# schematic.net
KiCad netlist of a schematic drawn in Altium Designer
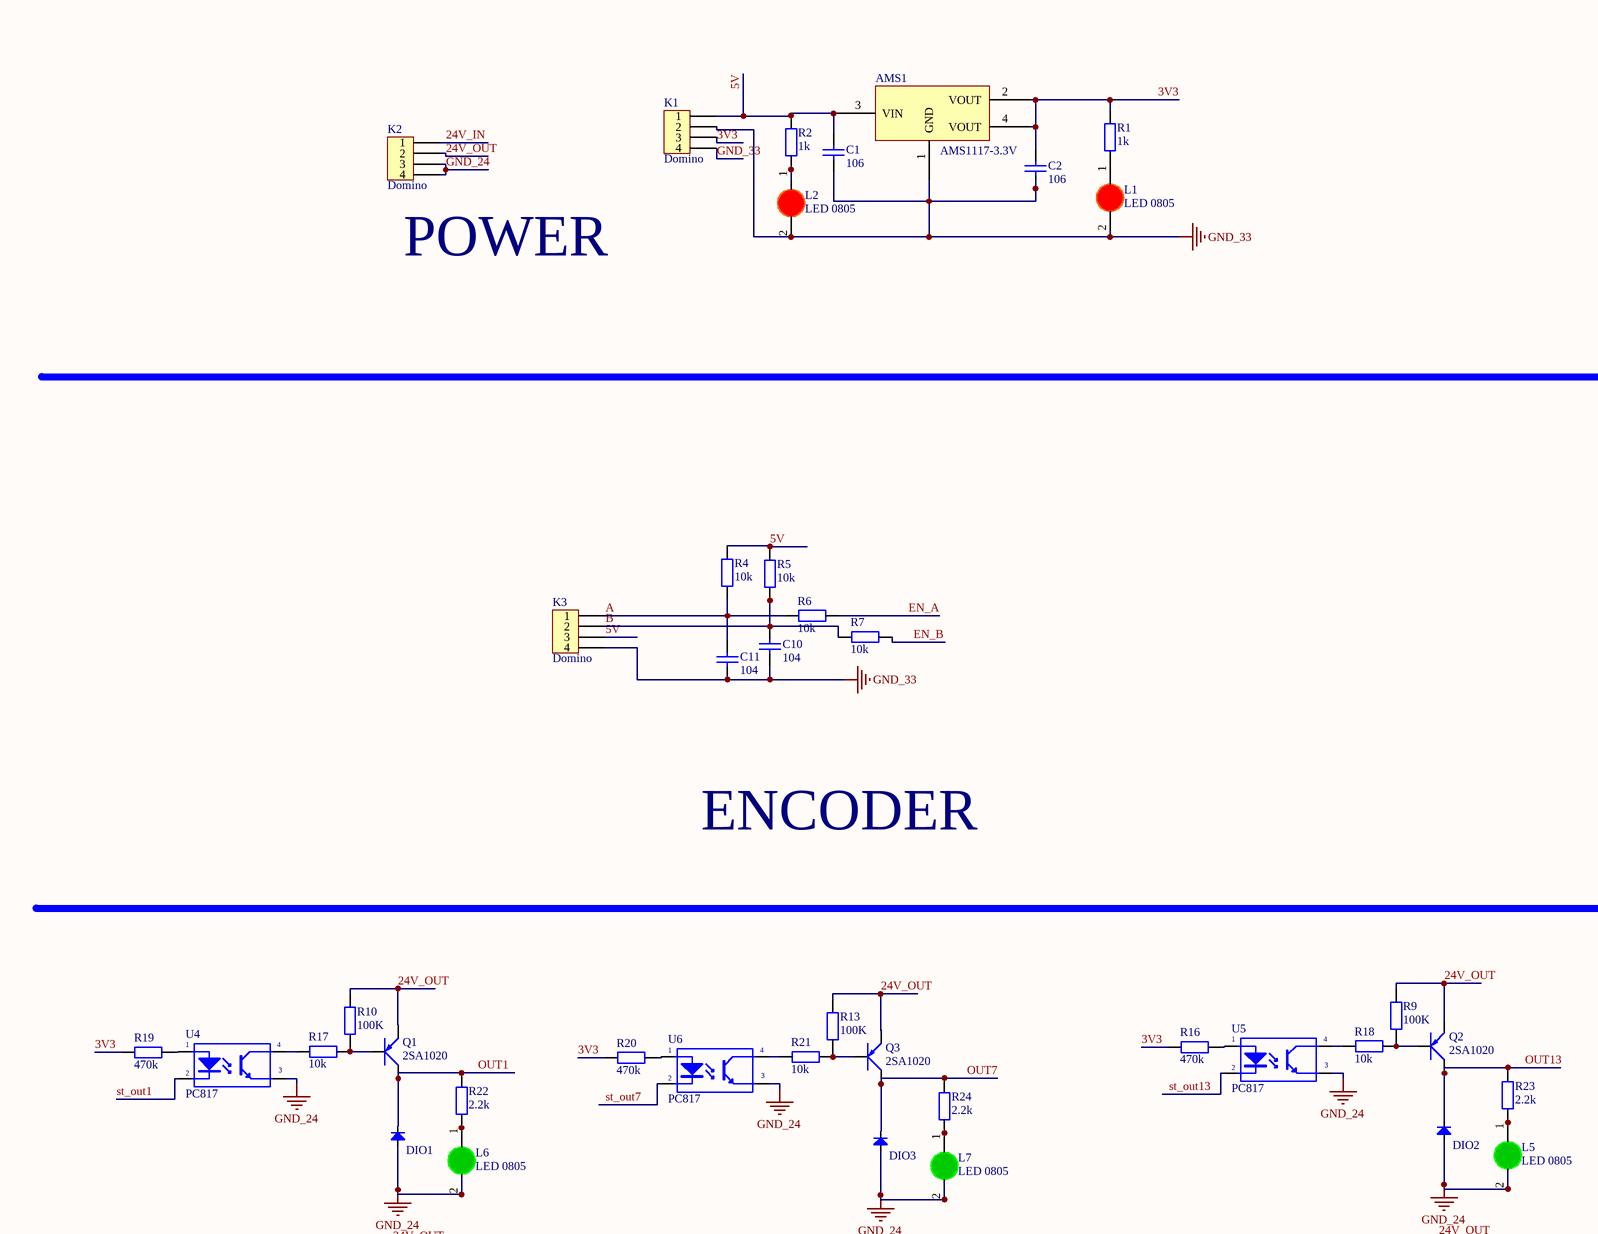
[diagram p0: schematic.SchDoc, top left]
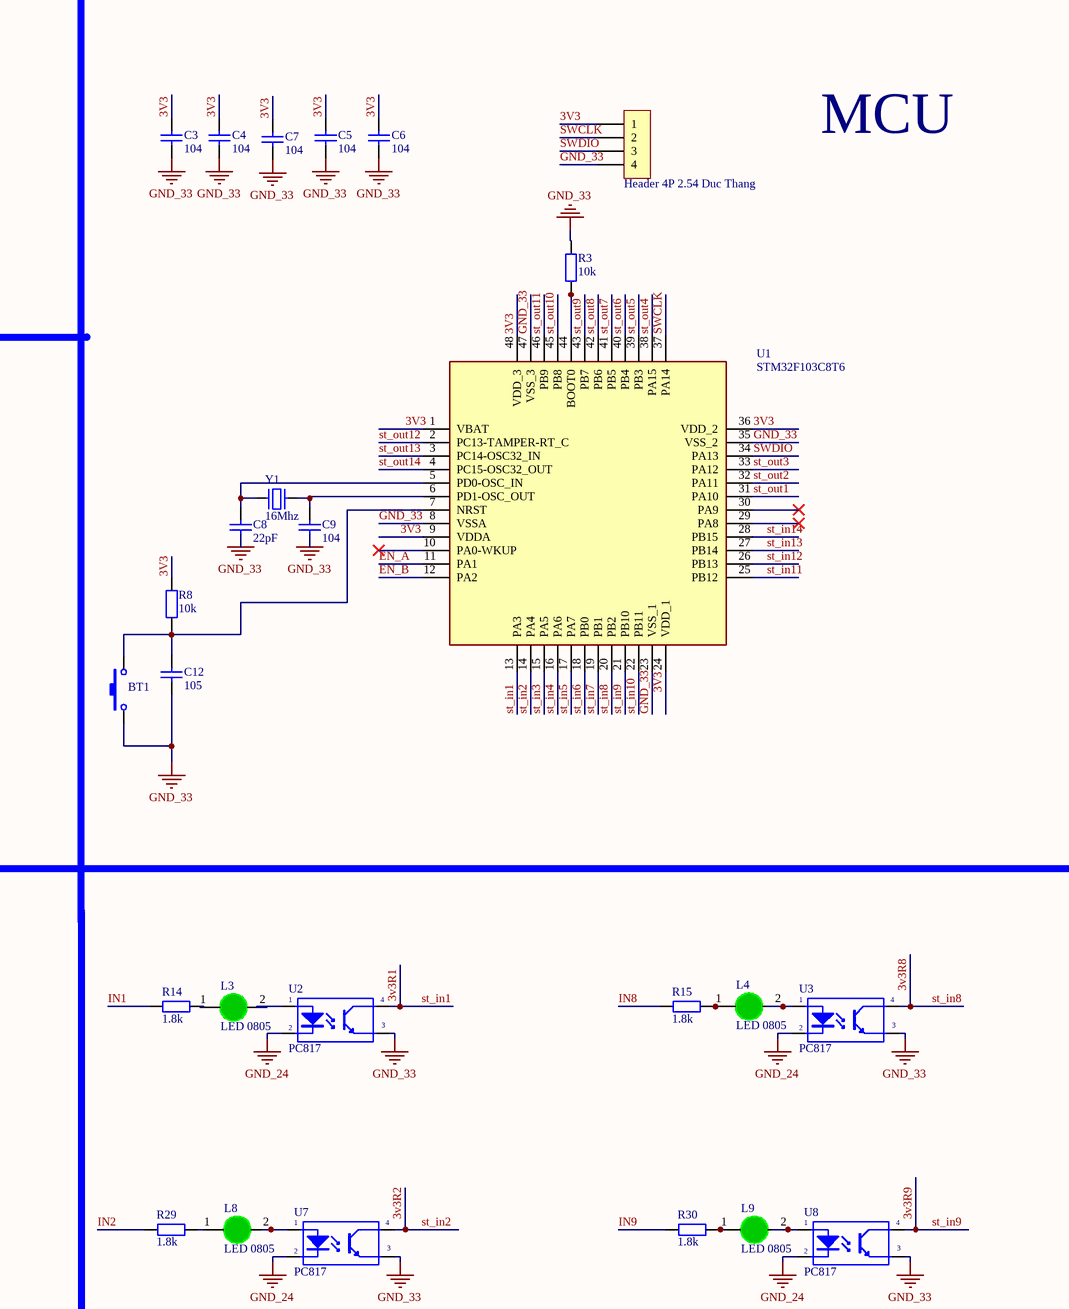
[diagram p1: schematic.SchDoc, top right]
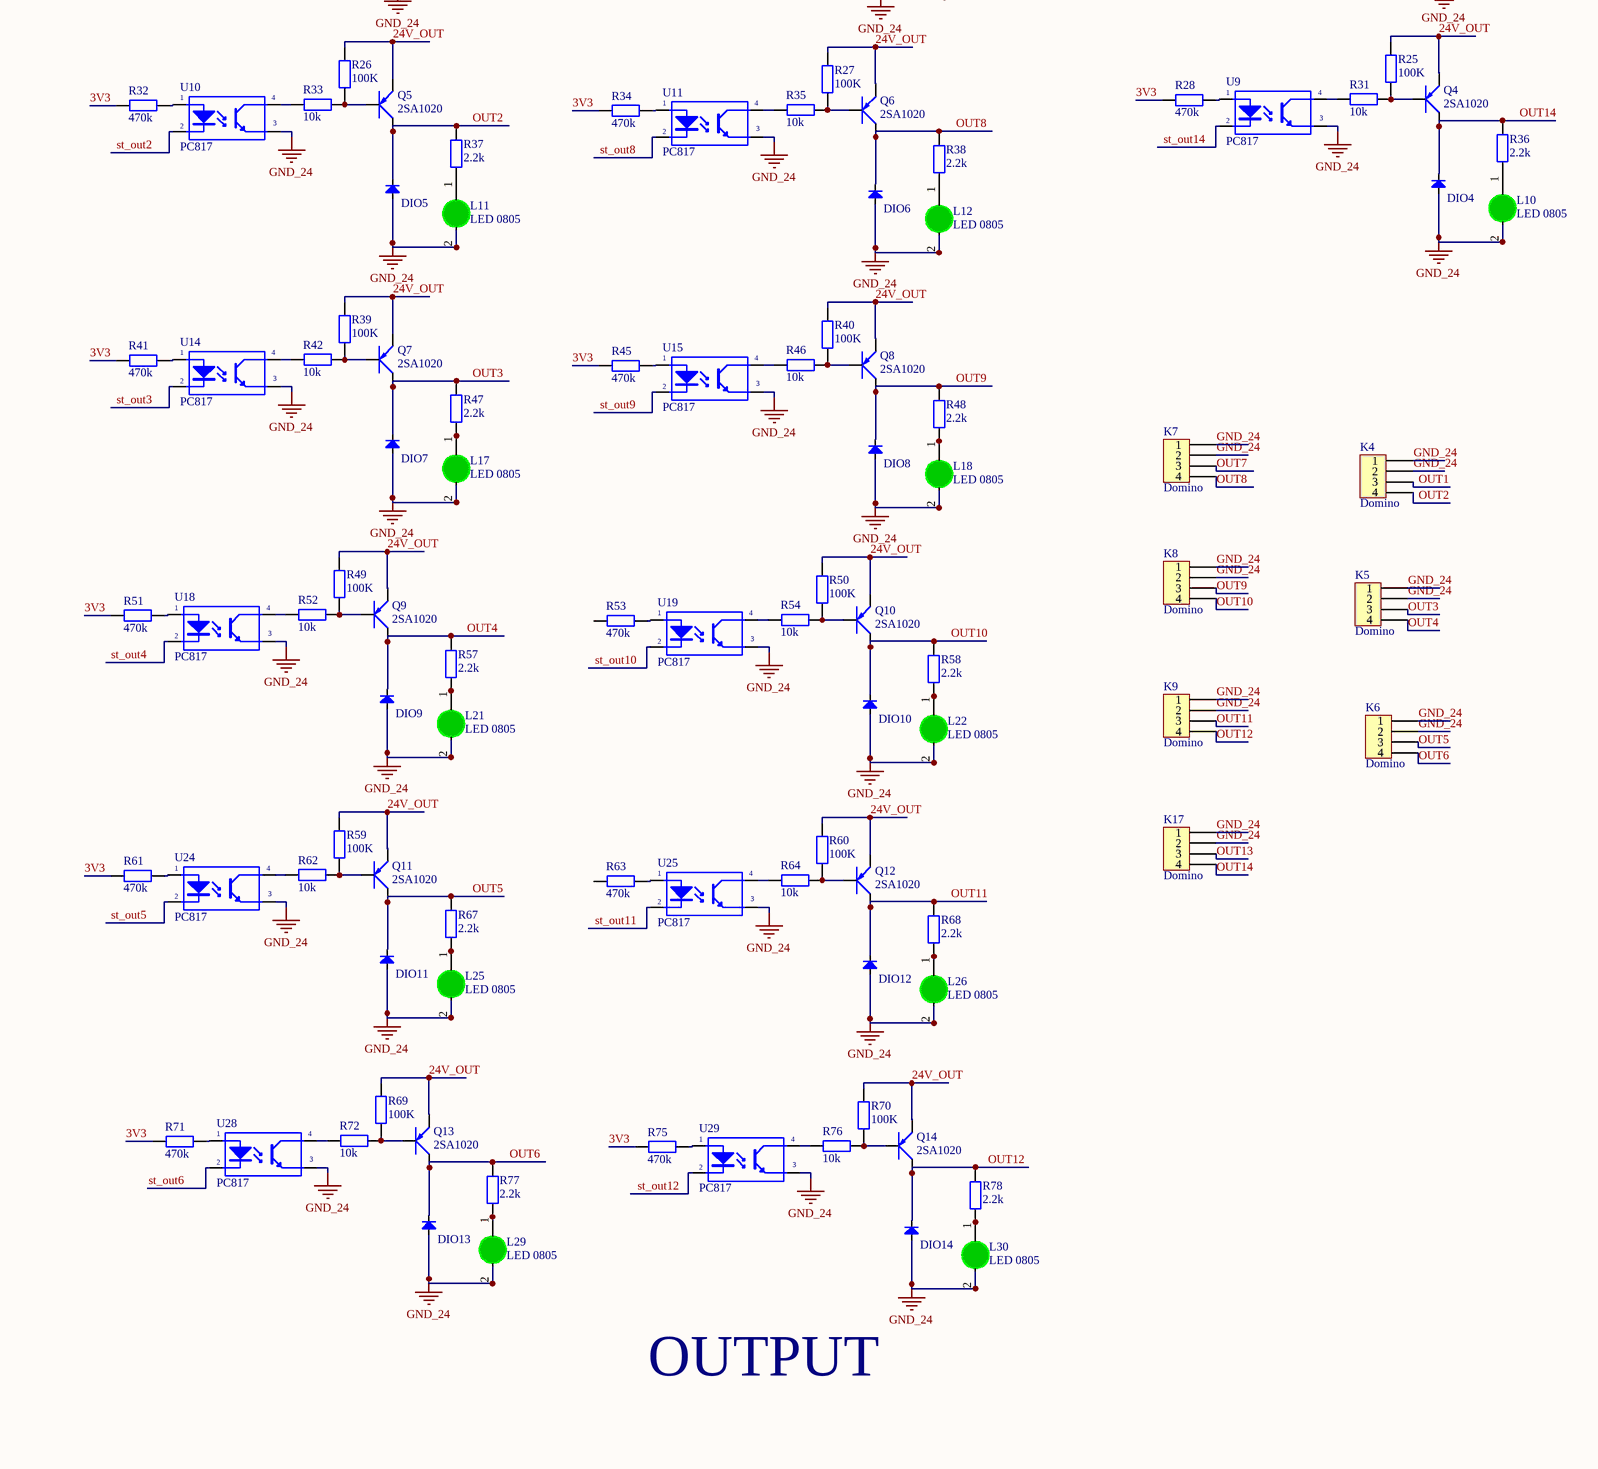
[diagram p2: schematic.SchDoc, bottom left]
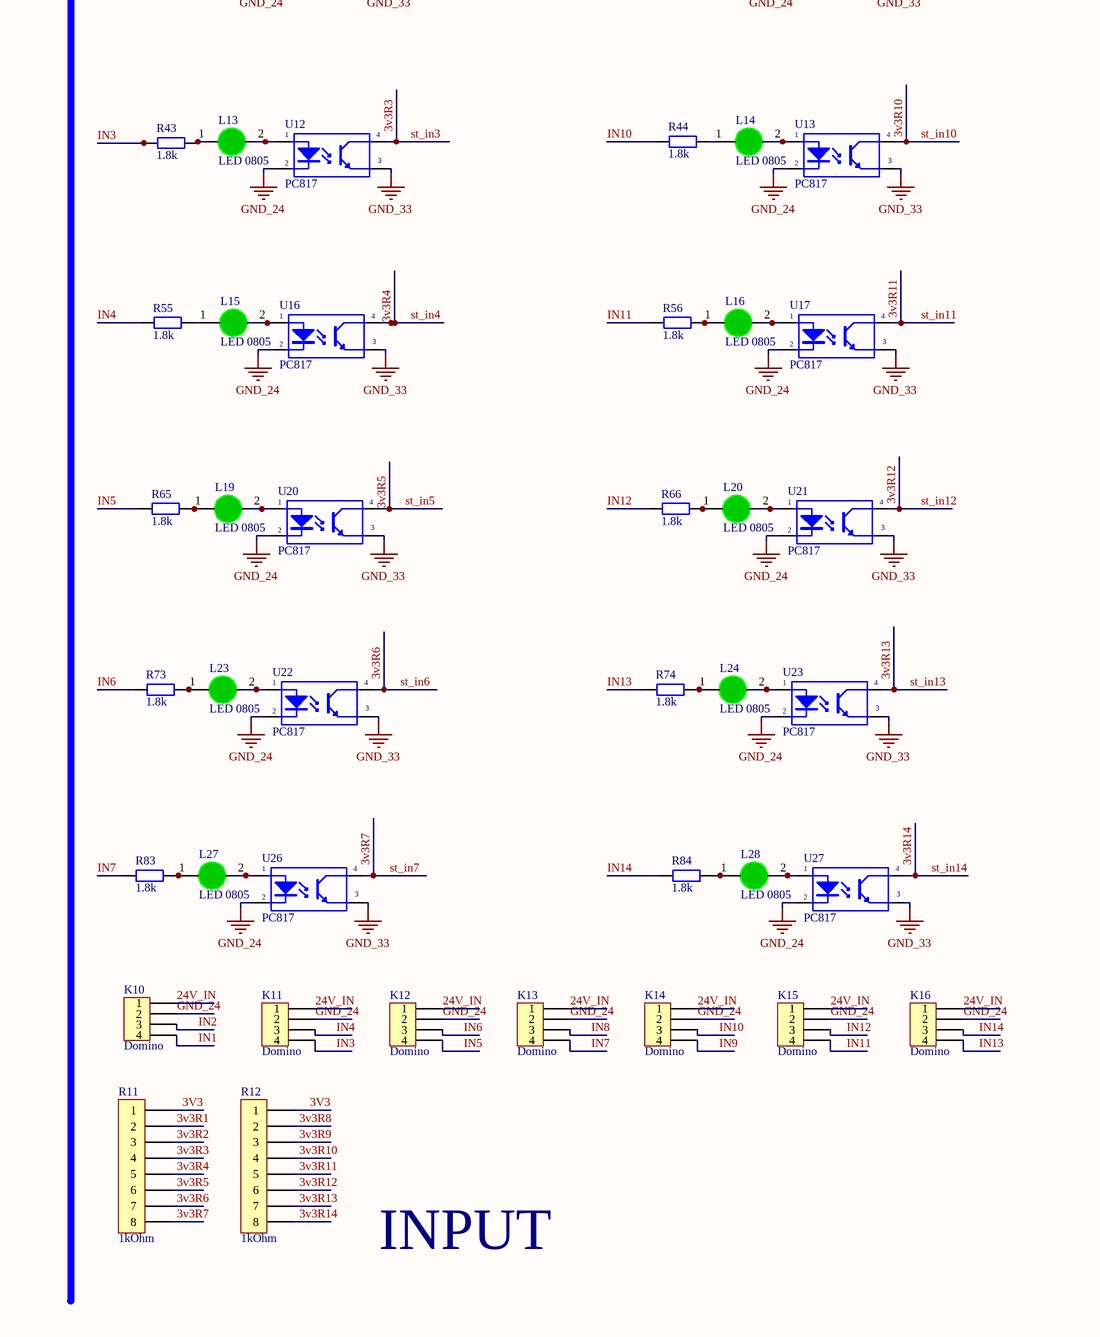
[diagram p3: schematic.SchDoc, bottom right]

(export (version "E")
  (design (tool "Eeschema 10.0.6"))
  (components
    (comp (ref "AMS1")
      (value "AMS1117-3.3V")
      (footprint "SOT223")
      (description "Dán")
      (libsource (lib "Altium_Lib_by_KhueNguyenCreator") (part "AMS1117 SMD"))
    )
    (comp (ref "BT1")
      (value "Nut Nhan 2 Chan SMD 3x6x2.5")
      (footprint "Nut Nhan 2 Chan SMD 3x6x2.5")
      (libsource (lib "Altium_Lib_by_KhueNguyenCreator") (part "Nut Nhan 2 Chan SMD 3x6x2.5"))
    )
    (comp (ref "C1")
      (value "106")
      (footprint "tu 1206")
      (description "Dán")
      (libsource (lib "Altium_Lib_by_KhueNguyenCreator") (part "Tu 1206 106 16V 20%"))
    )
    (comp (ref "C2")
      (value "106")
      (footprint "tu 1206")
      (description "Dán")
      (libsource (lib "Altium_Lib_by_KhueNguyenCreator") (part "Tu 1206 106 16V 20%"))
    )
    (comp (ref "C3")
      (value "104")
      (footprint "tu 1206")
      (description "Dán")
      (libsource (lib "Altium_Lib_by_KhueNguyenCreator") (part "Tu 1206 104 50V 20%"))
    )
    (comp (ref "C4")
      (value "104")
      (footprint "tu 1206")
      (description "Dán")
      (libsource (lib "Altium_Lib_by_KhueNguyenCreator") (part "Tu 1206 104 50V 20%"))
    )
    (comp (ref "C5")
      (value "104")
      (footprint "tu 1206")
      (description "Dán")
      (libsource (lib "Altium_Lib_by_KhueNguyenCreator") (part "Tu 1206 104 50V 20%"))
    )
    (comp (ref "C6")
      (value "104")
      (footprint "tu 1206")
      (description "Dán")
      (libsource (lib "Altium_Lib_by_KhueNguyenCreator") (part "Tu 1206 104 50V 20%"))
    )
    (comp (ref "C7")
      (value "104")
      (footprint "tu 1206")
      (description "Dán")
      (libsource (lib "Altium_Lib_by_KhueNguyenCreator") (part "Tu 1206 104 50V 20%"))
    )
    (comp (ref "C8")
      (value "22pF")
      (footprint "tu 1206")
      (description "Dán")
      (libsource (lib "Altium_Lib_by_KhueNguyenCreator") (part "Tu 1206 22pF 50V 10%"))
    )
    (comp (ref "C9")
      (value "104")
      (footprint "tu 1206")
      (description "Dán")
      (libsource (lib "Altium_Lib_by_KhueNguyenCreator") (part "Tu 1206 104 50V 20%"))
    )
    (comp (ref "C10")
      (value "104")
      (footprint "tu 1206")
      (description "Dán")
      (libsource (lib "Altium_Lib_by_KhueNguyenCreator") (part "Tu 1206 104 50V 20%"))
    )
    (comp (ref "C11")
      (value "104")
      (footprint "tu 1206")
      (description "Dán")
      (libsource (lib "Altium_Lib_by_KhueNguyenCreator") (part "Tu 1206 104 50V 20%"))
    )
    (comp (ref "C12")
      (value "105")
      (footprint "tu 1206")
      (description "Dán")
      (libsource (lib "Altium_Lib_by_KhueNguyenCreator") (part "Tu 1206 105 50V 20%"))
    )
    (comp (ref "DIO1")
      (value "Diode SMD")
      (footprint "DIO-SMD-123")
      (description "Default Diode")
      (fields (field (name "PUBLISHER") "Altium Limited"))
      (libsource (lib "TechMT.VN_Lib_Project v2") (part "Diode SMD"))
    )
    (comp (ref "DIO2")
      (value "Diode SMD")
      (footprint "DIO-SMD-123")
      (description "Default Diode")
      (fields (field (name "PUBLISHER") "Altium Limited"))
      (libsource (lib "TechMT.VN_Lib_Project v2") (part "Diode SMD"))
    )
    (comp (ref "DIO3")
      (value "Diode SMD")
      (footprint "DIO-SMD-123")
      (description "Default Diode")
      (fields (field (name "PUBLISHER") "Altium Limited"))
      (libsource (lib "TechMT.VN_Lib_Project v2") (part "Diode SMD"))
    )
    (comp (ref "DIO4")
      (value "Diode SMD")
      (footprint "DIO-SMD-123")
      (description "Default Diode")
      (fields (field (name "PUBLISHER") "Altium Limited"))
      (libsource (lib "TechMT.VN_Lib_Project v2") (part "Diode SMD"))
    )
    (comp (ref "DIO5")
      (value "Diode SMD")
      (footprint "DIO-SMD-123")
      (description "Default Diode")
      (fields (field (name "PUBLISHER") "Altium Limited"))
      (libsource (lib "TechMT.VN_Lib_Project v2") (part "Diode SMD"))
    )
    (comp (ref "DIO6")
      (value "Diode SMD")
      (footprint "DIO-SMD-123")
      (description "Default Diode")
      (fields (field (name "PUBLISHER") "Altium Limited"))
      (libsource (lib "TechMT.VN_Lib_Project v2") (part "Diode SMD"))
    )
    (comp (ref "DIO7")
      (value "Diode SMD")
      (footprint "DIO-SMD-123")
      (description "Default Diode")
      (fields (field (name "PUBLISHER") "Altium Limited"))
      (libsource (lib "TechMT.VN_Lib_Project v2") (part "Diode SMD"))
    )
    (comp (ref "DIO8")
      (value "Diode SMD")
      (footprint "DIO-SMD-123")
      (description "Default Diode")
      (fields (field (name "PUBLISHER") "Altium Limited"))
      (libsource (lib "TechMT.VN_Lib_Project v2") (part "Diode SMD"))
    )
    (comp (ref "DIO9")
      (value "Diode SMD")
      (footprint "DIO-SMD-123")
      (description "Default Diode")
      (fields (field (name "PUBLISHER") "Altium Limited"))
      (libsource (lib "TechMT.VN_Lib_Project v2") (part "Diode SMD"))
    )
    (comp (ref "DIO10")
      (value "Diode SMD")
      (footprint "DIO-SMD-123")
      (description "Default Diode")
      (fields (field (name "PUBLISHER") "Altium Limited"))
      (libsource (lib "TechMT.VN_Lib_Project v2") (part "Diode SMD"))
    )
    (comp (ref "DIO11")
      (value "Diode SMD")
      (footprint "DIO-SMD-123")
      (description "Default Diode")
      (fields (field (name "PUBLISHER") "Altium Limited"))
      (libsource (lib "TechMT.VN_Lib_Project v2") (part "Diode SMD"))
    )
    (comp (ref "DIO12")
      (value "Diode SMD")
      (footprint "DIO-SMD-123")
      (description "Default Diode")
      (fields (field (name "PUBLISHER") "Altium Limited"))
      (libsource (lib "TechMT.VN_Lib_Project v2") (part "Diode SMD"))
    )
    (comp (ref "DIO13")
      (value "Diode SMD")
      (footprint "DIO-SMD-123")
      (description "Default Diode")
      (fields (field (name "PUBLISHER") "Altium Limited"))
      (libsource (lib "TechMT.VN_Lib_Project v2") (part "Diode SMD"))
    )
    (comp (ref "DIO14")
      (value "Diode SMD")
      (footprint "DIO-SMD-123")
      (description "Default Diode")
      (fields (field (name "PUBLISHER") "Altium Limited"))
      (libsource (lib "TechMT.VN_Lib_Project v2") (part "Diode SMD"))
    )
    (comp (ref "H1")
      (value "Header 4P 2.54 Duc Thang")
      (footprint "XH2.54M-4")
      (description "Cắm")
      (libsource (lib "Altium_Lib_by_KhueNguyenCreator") (part "Header 4P 2.54 Duc Thang"))
    )
    (comp (ref "K1") (value "Domino") (footprint "KF128HL_2P") (libsource (lib "My_lib") (part "KF128HL_2P")))
    (comp (ref "K2") (value "Domino") (footprint "KF128HL_2P") (libsource (lib "My_lib") (part "KF128HL_2P")))
    (comp (ref "K3") (value "Domino") (footprint "KF128HL_2P") (libsource (lib "My_lib") (part "KF128HL_2P")))
    (comp (ref "K4") (value "Domino") (footprint "KF128HL_2P") (libsource (lib "My_lib") (part "KF128HL_2P")))
    (comp (ref "K5") (value "Domino") (footprint "KF128HL_2P") (libsource (lib "My_lib") (part "KF128HL_2P")))
    (comp (ref "K6") (value "Domino") (footprint "KF128HL_2P") (libsource (lib "My_lib") (part "KF128HL_2P")))
    (comp (ref "K7") (value "Domino") (footprint "KF128HL_2P") (libsource (lib "My_lib") (part "KF128HL_2P")))
    (comp (ref "K8") (value "Domino") (footprint "KF128HL_2P") (libsource (lib "My_lib") (part "KF128HL_2P")))
    (comp (ref "K9") (value "Domino") (footprint "KF128HL_2P") (libsource (lib "My_lib") (part "KF128HL_2P")))
    (comp (ref "K10")
      (value "Domino")
      (footprint "KF128HL_2P")
      (libsource (lib "My_lib") (part "KF128HL_2P"))
    )
    (comp (ref "K11")
      (value "Domino")
      (footprint "KF128HL_2P")
      (libsource (lib "My_lib") (part "KF128HL_2P"))
    )
    (comp (ref "K12")
      (value "Domino")
      (footprint "KF128HL_2P")
      (libsource (lib "My_lib") (part "KF128HL_2P"))
    )
    (comp (ref "K13")
      (value "Domino")
      (footprint "KF128HL_2P")
      (libsource (lib "My_lib") (part "KF128HL_2P"))
    )
    (comp (ref "K14")
      (value "Domino")
      (footprint "KF128HL_2P")
      (libsource (lib "My_lib") (part "KF128HL_2P"))
    )
    (comp (ref "K15")
      (value "Domino")
      (footprint "KF128HL_2P")
      (libsource (lib "My_lib") (part "KF128HL_2P"))
    )
    (comp (ref "K16")
      (value "Domino")
      (footprint "KF128HL_2P")
      (libsource (lib "My_lib") (part "KF128HL_2P"))
    )
    (comp (ref "K17")
      (value "Domino")
      (footprint "KF128HL_2P")
      (libsource (lib "My_lib") (part "KF128HL_2P"))
    )
    (comp (ref "L1")
      (value "LED 0805")
      (footprint "LED-1206-Red")
      (description "Dán")
      (libsource (lib "Altium_Lib_by_KhueNguyenCreator") (part "LED 1206 Do"))
    )
    (comp (ref "L2")
      (value "LED 0805")
      (footprint "LED-1206-Red")
      (description "Dán")
      (libsource (lib "Altium_Lib_by_KhueNguyenCreator") (part "LED 1206 Do"))
    )
    (comp (ref "L3")
      (value "LED 0805")
      (footprint "LED-1206-Green")
      (description "Dán")
      (libsource (lib "Altium_Lib_by_KhueNguyenCreator") (part "LED 1206 Xanh La"))
    )
    (comp (ref "L4")
      (value "LED 0805")
      (footprint "LED-1206-Green")
      (description "Dán")
      (libsource (lib "Altium_Lib_by_KhueNguyenCreator") (part "LED 1206 Xanh La"))
    )
    (comp (ref "L5")
      (value "LED 0805")
      (footprint "LED-1206-Green")
      (description "Dán")
      (libsource (lib "Altium_Lib_by_KhueNguyenCreator") (part "LED 1206 Xanh La"))
    )
    (comp (ref "L6")
      (value "LED 0805")
      (footprint "LED-1206-Green")
      (description "Dán")
      (libsource (lib "Altium_Lib_by_KhueNguyenCreator") (part "LED 1206 Xanh La"))
    )
    (comp (ref "L7")
      (value "LED 0805")
      (footprint "LED-1206-Green")
      (description "Dán")
      (libsource (lib "Altium_Lib_by_KhueNguyenCreator") (part "LED 1206 Xanh La"))
    )
    (comp (ref "L8")
      (value "LED 0805")
      (footprint "LED-1206-Green")
      (description "Dán")
      (libsource (lib "Altium_Lib_by_KhueNguyenCreator") (part "LED 1206 Xanh La"))
    )
    (comp (ref "L9")
      (value "LED 0805")
      (footprint "LED-1206-Green")
      (description "Dán")
      (libsource (lib "Altium_Lib_by_KhueNguyenCreator") (part "LED 1206 Xanh La"))
    )
    (comp (ref "L10")
      (value "LED 0805")
      (footprint "LED-1206-Green")
      (description "Dán")
      (libsource (lib "Altium_Lib_by_KhueNguyenCreator") (part "LED 1206 Xanh La"))
    )
    (comp (ref "L11")
      (value "LED 0805")
      (footprint "LED-1206-Green")
      (description "Dán")
      (libsource (lib "Altium_Lib_by_KhueNguyenCreator") (part "LED 1206 Xanh La"))
    )
    (comp (ref "L12")
      (value "LED 0805")
      (footprint "LED-1206-Green")
      (description "Dán")
      (libsource (lib "Altium_Lib_by_KhueNguyenCreator") (part "LED 1206 Xanh La"))
    )
    (comp (ref "L13")
      (value "LED 0805")
      (footprint "LED-1206-Green")
      (description "Dán")
      (libsource (lib "Altium_Lib_by_KhueNguyenCreator") (part "LED 1206 Xanh La"))
    )
    (comp (ref "L14")
      (value "LED 0805")
      (footprint "LED-1206-Green")
      (description "Dán")
      (libsource (lib "Altium_Lib_by_KhueNguyenCreator") (part "LED 1206 Xanh La"))
    )
    (comp (ref "L15")
      (value "LED 0805")
      (footprint "LED-1206-Green")
      (description "Dán")
      (libsource (lib "Altium_Lib_by_KhueNguyenCreator") (part "LED 1206 Xanh La"))
    )
    (comp (ref "L16")
      (value "LED 0805")
      (footprint "LED-1206-Green")
      (description "Dán")
      (libsource (lib "Altium_Lib_by_KhueNguyenCreator") (part "LED 1206 Xanh La"))
    )
    (comp (ref "L17")
      (value "LED 0805")
      (footprint "LED-1206-Green")
      (description "Dán")
      (libsource (lib "Altium_Lib_by_KhueNguyenCreator") (part "LED 1206 Xanh La"))
    )
    (comp (ref "L18")
      (value "LED 0805")
      (footprint "LED-1206-Green")
      (description "Dán")
      (libsource (lib "Altium_Lib_by_KhueNguyenCreator") (part "LED 1206 Xanh La"))
    )
    (comp (ref "L19")
      (value "LED 0805")
      (footprint "LED-1206-Green")
      (description "Dán")
      (libsource (lib "Altium_Lib_by_KhueNguyenCreator") (part "LED 1206 Xanh La"))
    )
    (comp (ref "L20")
      (value "LED 0805")
      (footprint "LED-1206-Green")
      (description "Dán")
      (libsource (lib "Altium_Lib_by_KhueNguyenCreator") (part "LED 1206 Xanh La"))
    )
    (comp (ref "L21")
      (value "LED 0805")
      (footprint "LED-1206-Green")
      (description "Dán")
      (libsource (lib "Altium_Lib_by_KhueNguyenCreator") (part "LED 1206 Xanh La"))
    )
    (comp (ref "L22")
      (value "LED 0805")
      (footprint "LED-1206-Green")
      (description "Dán")
      (libsource (lib "Altium_Lib_by_KhueNguyenCreator") (part "LED 1206 Xanh La"))
    )
    (comp (ref "L23")
      (value "LED 0805")
      (footprint "LED-1206-Green")
      (description "Dán")
      (libsource (lib "Altium_Lib_by_KhueNguyenCreator") (part "LED 1206 Xanh La"))
    )
    (comp (ref "L24")
      (value "LED 0805")
      (footprint "LED-1206-Green")
      (description "Dán")
      (libsource (lib "Altium_Lib_by_KhueNguyenCreator") (part "LED 1206 Xanh La"))
    )
    (comp (ref "L25")
      (value "LED 0805")
      (footprint "LED-1206-Green")
      (description "Dán")
      (libsource (lib "Altium_Lib_by_KhueNguyenCreator") (part "LED 1206 Xanh La"))
    )
    (comp (ref "L26")
      (value "LED 0805")
      (footprint "LED-1206-Green")
      (description "Dán")
      (libsource (lib "Altium_Lib_by_KhueNguyenCreator") (part "LED 1206 Xanh La"))
    )
    (comp (ref "L27")
      (value "LED 0805")
      (footprint "LED-1206-Green")
      (description "Dán")
      (libsource (lib "Altium_Lib_by_KhueNguyenCreator") (part "LED 1206 Xanh La"))
    )
    (comp (ref "L28")
      (value "LED 0805")
      (footprint "LED-1206-Green")
      (description "Dán")
      (libsource (lib "Altium_Lib_by_KhueNguyenCreator") (part "LED 1206 Xanh La"))
    )
    (comp (ref "L29")
      (value "LED 0805")
      (footprint "LED-1206-Green")
      (description "Dán")
      (libsource (lib "Altium_Lib_by_KhueNguyenCreator") (part "LED 1206 Xanh La"))
    )
    (comp (ref "L30")
      (value "LED 0805")
      (footprint "LED-1206-Green")
      (description "Dán")
      (libsource (lib "Altium_Lib_by_KhueNguyenCreator") (part "LED 1206 Xanh La"))
    )
    (comp (ref "Q1")
      (value "2SA1020")
      (footprint "TO92-123")
      (description "PNP 600mW, ECB")
      (libsource (lib "TechMT.VN_Lib_Project v2") (part "2SA1015"))
    )
    (comp (ref "Q2")
      (value "2SA1020")
      (footprint "TO92-123")
      (description "PNP 600mW, ECB")
      (libsource (lib "TechMT.VN_Lib_Project v2") (part "2SA1015"))
    )
    (comp (ref "Q3")
      (value "2SA1020")
      (footprint "TO92-123")
      (description "PNP 600mW, ECB")
      (libsource (lib "TechMT.VN_Lib_Project v2") (part "2SA1015"))
    )
    (comp (ref "Q4")
      (value "2SA1020")
      (footprint "TO92-123")
      (description "PNP 600mW, ECB")
      (libsource (lib "TechMT.VN_Lib_Project v2") (part "2SA1015"))
    )
    (comp (ref "Q5")
      (value "2SA1020")
      (footprint "TO92-123")
      (description "PNP 600mW, ECB")
      (libsource (lib "TechMT.VN_Lib_Project v2") (part "2SA1015"))
    )
    (comp (ref "Q6")
      (value "2SA1020")
      (footprint "TO92-123")
      (description "PNP 600mW, ECB")
      (libsource (lib "TechMT.VN_Lib_Project v2") (part "2SA1015"))
    )
    (comp (ref "Q7")
      (value "2SA1020")
      (footprint "TO92-123")
      (description "PNP 600mW, ECB")
      (libsource (lib "TechMT.VN_Lib_Project v2") (part "2SA1015"))
    )
    (comp (ref "Q8")
      (value "2SA1020")
      (footprint "TO92-123")
      (description "PNP 600mW, ECB")
      (libsource (lib "TechMT.VN_Lib_Project v2") (part "2SA1015"))
    )
    (comp (ref "Q9")
      (value "2SA1020")
      (footprint "TO92-123")
      (description "PNP 600mW, ECB")
      (libsource (lib "TechMT.VN_Lib_Project v2") (part "2SA1015"))
    )
    (comp (ref "Q10")
      (value "2SA1020")
      (footprint "TO92-123")
      (description "PNP 600mW, ECB")
      (libsource (lib "TechMT.VN_Lib_Project v2") (part "2SA1015"))
    )
    (comp (ref "Q11")
      (value "2SA1020")
      (footprint "TO92-123")
      (description "PNP 600mW, ECB")
      (libsource (lib "TechMT.VN_Lib_Project v2") (part "2SA1015"))
    )
    (comp (ref "Q12")
      (value "2SA1020")
      (footprint "TO92-123")
      (description "PNP 600mW, ECB")
      (libsource (lib "TechMT.VN_Lib_Project v2") (part "2SA1015"))
    )
    (comp (ref "Q13")
      (value "2SA1020")
      (footprint "TO92-123")
      (description "PNP 600mW, ECB")
      (libsource (lib "TechMT.VN_Lib_Project v2") (part "2SA1015"))
    )
    (comp (ref "Q14")
      (value "2SA1020")
      (footprint "TO92-123")
      (description "PNP 600mW, ECB")
      (libsource (lib "TechMT.VN_Lib_Project v2") (part "2SA1015"))
    )
    (comp (ref "R1")
      (value "1k")
      (footprint "tro smd 1206")
      (description "Dán")
      (libsource (lib "Altium_Lib_by_KhueNguyenCreator") (part "Tro 1206 5% 1k"))
    )
    (comp (ref "R2")
      (value "1k")
      (footprint "tro smd 1206")
      (description "Dán")
      (libsource (lib "Altium_Lib_by_KhueNguyenCreator") (part "Tro 1206 5% 1k"))
    )
    (comp (ref "R3")
      (value "10k")
      (footprint "tro smd 1206")
      (description "Dán")
      (libsource (lib "Altium_Lib_by_KhueNguyenCreator") (part "Tro 1206 5% 10k"))
    )
    (comp (ref "R4")
      (value "10k")
      (footprint "tro smd 1206")
      (description "Dán")
      (libsource (lib "Altium_Lib_by_KhueNguyenCreator") (part "Tro 1206 5% 10k"))
    )
    (comp (ref "R5")
      (value "10k")
      (footprint "tro smd 1206")
      (description "Dán")
      (libsource (lib "Altium_Lib_by_KhueNguyenCreator") (part "Tro 1206 5% 10k"))
    )
    (comp (ref "R6")
      (value "10k")
      (footprint "tro smd 1206")
      (description "Dán")
      (libsource (lib "Altium_Lib_by_KhueNguyenCreator") (part "Tro 1206 5% 10k"))
    )
    (comp (ref "R7")
      (value "10k")
      (footprint "tro smd 1206")
      (description "Dán")
      (libsource (lib "Altium_Lib_by_KhueNguyenCreator") (part "Tro 1206 5% 10k"))
    )
    (comp (ref "R8")
      (value "10k")
      (footprint "tro smd 1206")
      (description "Dán")
      (libsource (lib "Altium_Lib_by_KhueNguyenCreator") (part "Tro 1206 1% 10k"))
    )
    (comp (ref "R9")
      (value "100K")
      (footprint "tro smd 1206")
      (description "Dán")
      (libsource (lib "Altium_Lib_by_KhueNguyenCreator") (part "Tro 1206 5% 100K"))
    )
    (comp (ref "R10")
      (value "100K")
      (footprint "tro smd 1206")
      (description "Dán")
      (libsource (lib "Altium_Lib_by_KhueNguyenCreator") (part "Tro 1206 5% 100K"))
    )
    (comp (ref "R11")
      (value "1kOhm")
      (footprint "resistor_bar")
      (description "resistor bar 1kOhm")
      (libsource (lib "My_lib") (part "resistor_bar"))
    )
    (comp (ref "R12")
      (value "1kOhm")
      (footprint "resistor_bar")
      (description "resistor bar 1kOhm")
      (libsource (lib "My_lib") (part "resistor_bar"))
    )
    (comp (ref "R13")
      (value "100K")
      (footprint "tro smd 1206")
      (description "Dán")
      (libsource (lib "Altium_Lib_by_KhueNguyenCreator") (part "Tro 1206 5% 100K"))
    )
    (comp (ref "R14")
      (value "1.8k")
      (footprint "tro smd 1206")
      (description "Dán")
      (libsource (lib "Altium_Lib_by_KhueNguyenCreator") (part "Tro 1206 1% 2k"))
    )
    (comp (ref "R15")
      (value "1.8k")
      (footprint "tro smd 1206")
      (description "Dán")
      (libsource (lib "Altium_Lib_by_KhueNguyenCreator") (part "Tro 1206 1% 2k"))
    )
    (comp (ref "R16")
      (value "470k")
      (footprint "tro smd 1206")
      (description "Dán")
      (libsource (lib "Altium_Lib_by_KhueNguyenCreator") (part "Tro 1206 1% 470k"))
    )
    (comp (ref "R17")
      (value "10k")
      (footprint "tro smd 1206")
      (description "Dán")
      (libsource (lib "Altium_Lib_by_KhueNguyenCreator") (part "Tro 1206 5% 10k"))
    )
    (comp (ref "R18")
      (value "10k")
      (footprint "tro smd 1206")
      (description "Dán")
      (libsource (lib "Altium_Lib_by_KhueNguyenCreator") (part "Tro 1206 5% 10k"))
    )
    (comp (ref "R19")
      (value "470k")
      (footprint "tro smd 1206")
      (description "Dán")
      (libsource (lib "Altium_Lib_by_KhueNguyenCreator") (part "Tro 1206 1% 470k"))
    )
    (comp (ref "R20")
      (value "470k")
      (footprint "tro smd 1206")
      (description "Dán")
      (libsource (lib "Altium_Lib_by_KhueNguyenCreator") (part "Tro 1206 1% 470k"))
    )
    (comp (ref "R21")
      (value "10k")
      (footprint "tro smd 1206")
      (description "Dán")
      (libsource (lib "Altium_Lib_by_KhueNguyenCreator") (part "Tro 1206 5% 10k"))
    )
    (comp (ref "R22")
      (value "2.2k")
      (footprint "tro smd 1206")
      (description "Dán")
      (libsource (lib "Altium_Lib_by_KhueNguyenCreator") (part "Tro 1206 1% 2.2k"))
    )
    (comp (ref "R23")
      (value "2.2k")
      (footprint "tro smd 1206")
      (description "Dán")
      (libsource (lib "Altium_Lib_by_KhueNguyenCreator") (part "Tro 1206 1% 2.2k"))
    )
    (comp (ref "R24")
      (value "2.2k")
      (footprint "tro smd 1206")
      (description "Dán")
      (libsource (lib "Altium_Lib_by_KhueNguyenCreator") (part "Tro 1206 1% 2.2k"))
    )
    (comp (ref "R25")
      (value "100K")
      (footprint "tro smd 1206")
      (description "Dán")
      (libsource (lib "Altium_Lib_by_KhueNguyenCreator") (part "Tro 1206 5% 100K"))
    )
    (comp (ref "R26")
      (value "100K")
      (footprint "tro smd 1206")
      (description "Dán")
      (libsource (lib "Altium_Lib_by_KhueNguyenCreator") (part "Tro 1206 5% 100K"))
    )
    (comp (ref "R27")
      (value "100K")
      (footprint "tro smd 1206")
      (description "Dán")
      (libsource (lib "Altium_Lib_by_KhueNguyenCreator") (part "Tro 1206 5% 100K"))
    )
    (comp (ref "R28")
      (value "470k")
      (footprint "tro smd 1206")
      (description "Dán")
      (libsource (lib "Altium_Lib_by_KhueNguyenCreator") (part "Tro 1206 1% 470k"))
    )
    (comp (ref "R29")
      (value "1.8k")
      (footprint "tro smd 1206")
      (description "Dán")
      (libsource (lib "Altium_Lib_by_KhueNguyenCreator") (part "Tro 1206 1% 2k"))
    )
    (comp (ref "R30")
      (value "1.8k")
      (footprint "tro smd 1206")
      (description "Dán")
      (libsource (lib "Altium_Lib_by_KhueNguyenCreator") (part "Tro 1206 1% 2k"))
    )
    (comp (ref "R31")
      (value "10k")
      (footprint "tro smd 1206")
      (description "Dán")
      (libsource (lib "Altium_Lib_by_KhueNguyenCreator") (part "Tro 1206 5% 10k"))
    )
    (comp (ref "R32")
      (value "470k")
      (footprint "tro smd 1206")
      (description "Dán")
      (libsource (lib "Altium_Lib_by_KhueNguyenCreator") (part "Tro 1206 1% 470k"))
    )
    (comp (ref "R33")
      (value "10k")
      (footprint "tro smd 1206")
      (description "Dán")
      (libsource (lib "Altium_Lib_by_KhueNguyenCreator") (part "Tro 1206 5% 10k"))
    )
    (comp (ref "R34")
      (value "470k")
      (footprint "tro smd 1206")
      (description "Dán")
      (libsource (lib "Altium_Lib_by_KhueNguyenCreator") (part "Tro 1206 1% 470k"))
    )
    (comp (ref "R35")
      (value "10k")
      (footprint "tro smd 1206")
      (description "Dán")
      (libsource (lib "Altium_Lib_by_KhueNguyenCreator") (part "Tro 1206 5% 10k"))
    )
    (comp (ref "R36")
      (value "2.2k")
      (footprint "tro smd 1206")
      (description "Dán")
      (libsource (lib "Altium_Lib_by_KhueNguyenCreator") (part "Tro 1206 1% 2.2k"))
    )
    (comp (ref "R37")
      (value "2.2k")
      (footprint "tro smd 1206")
      (description "Dán")
      (libsource (lib "Altium_Lib_by_KhueNguyenCreator") (part "Tro 1206 1% 2.2k"))
    )
    (comp (ref "R38")
      (value "2.2k")
      (footprint "tro smd 1206")
      (description "Dán")
      (libsource (lib "Altium_Lib_by_KhueNguyenCreator") (part "Tro 1206 1% 2.2k"))
    )
    (comp (ref "R39")
      (value "100K")
      (footprint "tro smd 1206")
      (description "Dán")
      (libsource (lib "Altium_Lib_by_KhueNguyenCreator") (part "Tro 1206 5% 100K"))
    )
    (comp (ref "R40")
      (value "100K")
      (footprint "tro smd 1206")
      (description "Dán")
      (libsource (lib "Altium_Lib_by_KhueNguyenCreator") (part "Tro 1206 5% 100K"))
    )
    (comp (ref "R41")
      (value "470k")
      (footprint "tro smd 1206")
      (description "Dán")
      (libsource (lib "Altium_Lib_by_KhueNguyenCreator") (part "Tro 1206 1% 470k"))
    )
    (comp (ref "R42")
      (value "10k")
      (footprint "tro smd 1206")
      (description "Dán")
      (libsource (lib "Altium_Lib_by_KhueNguyenCreator") (part "Tro 1206 5% 10k"))
    )
    (comp (ref "R43")
      (value "1.8k")
      (footprint "tro smd 1206")
      (description "Dán")
      (libsource (lib "Altium_Lib_by_KhueNguyenCreator") (part "Tro 1206 1% 2k"))
    )
    (comp (ref "R44")
      (value "1.8k")
      (footprint "tro smd 1206")
      (description "Dán")
      (libsource (lib "Altium_Lib_by_KhueNguyenCreator") (part "Tro 1206 1% 2k"))
    )
    (comp (ref "R45")
      (value "470k")
      (footprint "tro smd 1206")
      (description "Dán")
      (libsource (lib "Altium_Lib_by_KhueNguyenCreator") (part "Tro 1206 1% 470k"))
    )
    (comp (ref "R46")
      (value "10k")
      (footprint "tro smd 1206")
      (description "Dán")
      (libsource (lib "Altium_Lib_by_KhueNguyenCreator") (part "Tro 1206 5% 10k"))
    )
    (comp (ref "R47")
      (value "2.2k")
      (footprint "tro smd 1206")
      (description "Dán")
      (libsource (lib "Altium_Lib_by_KhueNguyenCreator") (part "Tro 1206 1% 2.2k"))
    )
    (comp (ref "R48")
      (value "2.2k")
      (footprint "tro smd 1206")
      (description "Dán")
      (libsource (lib "Altium_Lib_by_KhueNguyenCreator") (part "Tro 1206 1% 2.2k"))
    )
    (comp (ref "R49")
      (value "100K")
      (footprint "tro smd 1206")
      (description "Dán")
      (libsource (lib "Altium_Lib_by_KhueNguyenCreator") (part "Tro 1206 5% 100K"))
    )
    (comp (ref "R50")
      (value "100K")
      (footprint "tro smd 1206")
      (description "Dán")
      (libsource (lib "Altium_Lib_by_KhueNguyenCreator") (part "Tro 1206 5% 100K"))
    )
    (comp (ref "R51")
      (value "470k")
      (footprint "tro smd 1206")
      (description "Dán")
      (libsource (lib "Altium_Lib_by_KhueNguyenCreator") (part "Tro 1206 1% 470k"))
    )
    (comp (ref "R52")
      (value "10k")
      (footprint "tro smd 1206")
      (description "Dán")
      (libsource (lib "Altium_Lib_by_KhueNguyenCreator") (part "Tro 1206 5% 10k"))
    )
    (comp (ref "R53")
      (value "470k")
      (footprint "tro smd 1206")
      (description "Dán")
      (libsource (lib "Altium_Lib_by_KhueNguyenCreator") (part "Tro 1206 1% 470k"))
    )
    (comp (ref "R54")
      (value "10k")
      (footprint "tro smd 1206")
      (description "Dán")
      (libsource (lib "Altium_Lib_by_KhueNguyenCreator") (part "Tro 1206 5% 10k"))
    )
    (comp (ref "R55")
      (value "1.8k")
      (footprint "tro smd 1206")
      (description "Dán")
      (libsource (lib "Altium_Lib_by_KhueNguyenCreator") (part "Tro 1206 1% 2k"))
    )
    (comp (ref "R56")
      (value "1.8k")
      (footprint "tro smd 1206")
      (description "Dán")
      (libsource (lib "Altium_Lib_by_KhueNguyenCreator") (part "Tro 1206 1% 2k"))
    )
    (comp (ref "R57")
      (value "2.2k")
      (footprint "tro smd 1206")
      (description "Dán")
      (libsource (lib "Altium_Lib_by_KhueNguyenCreator") (part "Tro 1206 1% 2.2k"))
    )
    (comp (ref "R58")
      (value "2.2k")
      (footprint "tro smd 1206")
      (description "Dán")
      (libsource (lib "Altium_Lib_by_KhueNguyenCreator") (part "Tro 1206 1% 2.2k"))
    )
    (comp (ref "R59")
      (value "100K")
      (footprint "tro smd 1206")
      (description "Dán")
      (libsource (lib "Altium_Lib_by_KhueNguyenCreator") (part "Tro 1206 5% 100K"))
    )
    (comp (ref "R60")
      (value "100K")
      (footprint "tro smd 1206")
      (description "Dán")
      (libsource (lib "Altium_Lib_by_KhueNguyenCreator") (part "Tro 1206 5% 100K"))
    )
    (comp (ref "R61")
      (value "470k")
      (footprint "tro smd 1206")
      (description "Dán")
      (libsource (lib "Altium_Lib_by_KhueNguyenCreator") (part "Tro 1206 1% 470k"))
    )
    (comp (ref "R62")
      (value "10k")
      (footprint "tro smd 1206")
      (description "Dán")
      (libsource (lib "Altium_Lib_by_KhueNguyenCreator") (part "Tro 1206 5% 10k"))
    )
    (comp (ref "R63")
      (value "470k")
      (footprint "tro smd 1206")
      (description "Dán")
      (libsource (lib "Altium_Lib_by_KhueNguyenCreator") (part "Tro 1206 1% 470k"))
    )
    (comp (ref "R64")
      (value "10k")
      (footprint "tro smd 1206")
      (description "Dán")
      (libsource (lib "Altium_Lib_by_KhueNguyenCreator") (part "Tro 1206 5% 10k"))
    )
    (comp (ref "R65")
      (value "1.8k")
      (footprint "tro smd 1206")
      (description "Dán")
      (libsource (lib "Altium_Lib_by_KhueNguyenCreator") (part "Tro 1206 1% 2k"))
    )
    (comp (ref "R66")
      (value "1.8k")
      (footprint "tro smd 1206")
      (description "Dán")
      (libsource (lib "Altium_Lib_by_KhueNguyenCreator") (part "Tro 1206 1% 2k"))
    )
    (comp (ref "R67")
      (value "2.2k")
      (footprint "tro smd 1206")
      (description "Dán")
      (libsource (lib "Altium_Lib_by_KhueNguyenCreator") (part "Tro 1206 1% 2.2k"))
    )
    (comp (ref "R68")
      (value "2.2k")
      (footprint "tro smd 1206")
      (description "Dán")
      (libsource (lib "Altium_Lib_by_KhueNguyenCreator") (part "Tro 1206 1% 2.2k"))
    )
    (comp (ref "R69")
      (value "100K")
      (footprint "tro smd 1206")
      (description "Dán")
      (libsource (lib "Altium_Lib_by_KhueNguyenCreator") (part "Tro 1206 5% 100K"))
    )
    (comp (ref "R70")
      (value "100K")
      (footprint "tro smd 1206")
      (description "Dán")
      (libsource (lib "Altium_Lib_by_KhueNguyenCreator") (part "Tro 1206 5% 100K"))
    )
    (comp (ref "R71")
      (value "470k")
      (footprint "tro smd 1206")
      (description "Dán")
      (libsource (lib "Altium_Lib_by_KhueNguyenCreator") (part "Tro 1206 1% 470k"))
    )
    (comp (ref "R72")
      (value "10k")
      (footprint "tro smd 1206")
      (description "Dán")
      (libsource (lib "Altium_Lib_by_KhueNguyenCreator") (part "Tro 1206 5% 10k"))
    )
    (comp (ref "R73")
      (value "1.8k")
      (footprint "tro smd 1206")
      (description "Dán")
      (libsource (lib "Altium_Lib_by_KhueNguyenCreator") (part "Tro 1206 1% 2k"))
    )
    (comp (ref "R74")
      (value "1.8k")
      (footprint "tro smd 1206")
      (description "Dán")
      (libsource (lib "Altium_Lib_by_KhueNguyenCreator") (part "Tro 1206 1% 2k"))
    )
    (comp (ref "R75")
      (value "470k")
      (footprint "tro smd 1206")
      (description "Dán")
      (libsource (lib "Altium_Lib_by_KhueNguyenCreator") (part "Tro 1206 1% 470k"))
    )
    (comp (ref "R76")
      (value "10k")
      (footprint "tro smd 1206")
      (description "Dán")
      (libsource (lib "Altium_Lib_by_KhueNguyenCreator") (part "Tro 1206 5% 10k"))
    )
    (comp (ref "R77")
      (value "2.2k")
      (footprint "tro smd 1206")
      (description "Dán")
      (libsource (lib "Altium_Lib_by_KhueNguyenCreator") (part "Tro 1206 1% 2.2k"))
    )
    (comp (ref "R78")
      (value "2.2k")
      (footprint "tro smd 1206")
      (description "Dán")
      (libsource (lib "Altium_Lib_by_KhueNguyenCreator") (part "Tro 1206 1% 2.2k"))
    )
    (comp (ref "R83")
      (value "1.8k")
      (footprint "tro smd 1206")
      (description "Dán")
      (libsource (lib "Altium_Lib_by_KhueNguyenCreator") (part "Tro 1206 1% 2k"))
    )
    (comp (ref "R84")
      (value "1.8k")
      (footprint "tro smd 1206")
      (description "Dán")
      (libsource (lib "Altium_Lib_by_KhueNguyenCreator") (part "Tro 1206 1% 2k"))
    )
    (comp (ref "U1")
      (value "STM32F103C8T6")
      (footprint "LQFP-48_19.6_393_58X11_SMD")
      (description "ARM® Cortex®-M3 STM32F1 Microcontroller IC 32-Bit 72MHz 64KB (64K x 8) FLASH 48-LQFP (7x7)")
      (fields (field (name "MANUFACTURER") "STMicroelectronics"))
      (libsource (lib "Altium_Lib_by_KhueNguyenCreator") (part "IC_STM32F103C8T6"))
    )
    (comp (ref "U2")
      (value "PC817")
      (footprint "DIP4")
      (description "Single Opto")
      (libsource (lib "TechMT.VN_Lib_Project v2") (part "PC817"))
    )
    (comp (ref "U3")
      (value "PC817")
      (footprint "DIP4")
      (description "Single Opto")
      (libsource (lib "TechMT.VN_Lib_Project v2") (part "PC817"))
    )
    (comp (ref "U4")
      (value "PC817")
      (footprint "DIP4")
      (description "Single Opto")
      (libsource (lib "TechMT.VN_Lib_Project v2") (part "PC817"))
    )
    (comp (ref "U5")
      (value "PC817")
      (footprint "DIP4")
      (description "Single Opto")
      (libsource (lib "TechMT.VN_Lib_Project v2") (part "PC817"))
    )
    (comp (ref "U6")
      (value "PC817")
      (footprint "DIP4")
      (description "Single Opto")
      (libsource (lib "TechMT.VN_Lib_Project v2") (part "PC817"))
    )
    (comp (ref "U7")
      (value "PC817")
      (footprint "DIP4")
      (description "Single Opto")
      (libsource (lib "TechMT.VN_Lib_Project v2") (part "PC817"))
    )
    (comp (ref "U8")
      (value "PC817")
      (footprint "DIP4")
      (description "Single Opto")
      (libsource (lib "TechMT.VN_Lib_Project v2") (part "PC817"))
    )
    (comp (ref "U9")
      (value "PC817")
      (footprint "DIP4")
      (description "Single Opto")
      (libsource (lib "TechMT.VN_Lib_Project v2") (part "PC817"))
    )
    (comp (ref "U10")
      (value "PC817")
      (footprint "DIP4")
      (description "Single Opto")
      (libsource (lib "TechMT.VN_Lib_Project v2") (part "PC817"))
    )
    (comp (ref "U11")
      (value "PC817")
      (footprint "DIP4")
      (description "Single Opto")
      (libsource (lib "TechMT.VN_Lib_Project v2") (part "PC817"))
    )
    (comp (ref "U12")
      (value "PC817")
      (footprint "DIP4")
      (description "Single Opto")
      (libsource (lib "TechMT.VN_Lib_Project v2") (part "PC817"))
    )
    (comp (ref "U13")
      (value "PC817")
      (footprint "DIP4")
      (description "Single Opto")
      (libsource (lib "TechMT.VN_Lib_Project v2") (part "PC817"))
    )
    (comp (ref "U14")
      (value "PC817")
      (footprint "DIP4")
      (description "Single Opto")
      (libsource (lib "TechMT.VN_Lib_Project v2") (part "PC817"))
    )
    (comp (ref "U15")
      (value "PC817")
      (footprint "DIP4")
      (description "Single Opto")
      (libsource (lib "TechMT.VN_Lib_Project v2") (part "PC817"))
    )
    (comp (ref "U16")
      (value "PC817")
      (footprint "DIP4")
      (description "Single Opto")
      (libsource (lib "TechMT.VN_Lib_Project v2") (part "PC817"))
    )
    (comp (ref "U17")
      (value "PC817")
      (footprint "DIP4")
      (description "Single Opto")
      (libsource (lib "TechMT.VN_Lib_Project v2") (part "PC817"))
    )
    (comp (ref "U18")
      (value "PC817")
      (footprint "DIP4")
      (description "Single Opto")
      (libsource (lib "TechMT.VN_Lib_Project v2") (part "PC817"))
    )
    (comp (ref "U19")
      (value "PC817")
      (footprint "DIP4")
      (description "Single Opto")
      (libsource (lib "TechMT.VN_Lib_Project v2") (part "PC817"))
    )
    (comp (ref "U20")
      (value "PC817")
      (footprint "DIP4")
      (description "Single Opto")
      (libsource (lib "TechMT.VN_Lib_Project v2") (part "PC817"))
    )
    (comp (ref "U21")
      (value "PC817")
      (footprint "DIP4")
      (description "Single Opto")
      (libsource (lib "TechMT.VN_Lib_Project v2") (part "PC817"))
    )
    (comp (ref "U22")
      (value "PC817")
      (footprint "DIP4")
      (description "Single Opto")
      (libsource (lib "TechMT.VN_Lib_Project v2") (part "PC817"))
    )
    (comp (ref "U23")
      (value "PC817")
      (footprint "DIP4")
      (description "Single Opto")
      (libsource (lib "TechMT.VN_Lib_Project v2") (part "PC817"))
    )
    (comp (ref "U24")
      (value "PC817")
      (footprint "DIP4")
      (description "Single Opto")
      (libsource (lib "TechMT.VN_Lib_Project v2") (part "PC817"))
    )
    (comp (ref "U25")
      (value "PC817")
      (footprint "DIP4")
      (description "Single Opto")
      (libsource (lib "TechMT.VN_Lib_Project v2") (part "PC817"))
    )
    (comp (ref "U26")
      (value "PC817")
      (footprint "DIP4")
      (description "Single Opto")
      (libsource (lib "TechMT.VN_Lib_Project v2") (part "PC817"))
    )
    (comp (ref "U27")
      (value "PC817")
      (footprint "DIP4")
      (description "Single Opto")
      (libsource (lib "TechMT.VN_Lib_Project v2") (part "PC817"))
    )
    (comp (ref "U28")
      (value "PC817")
      (footprint "DIP4")
      (description "Single Opto")
      (libsource (lib "TechMT.VN_Lib_Project v2") (part "PC817"))
    )
    (comp (ref "U29")
      (value "PC817")
      (footprint "DIP4")
      (description "Single Opto")
      (libsource (lib "TechMT.VN_Lib_Project v2") (part "PC817"))
    )
    (comp (ref "Y1")
      (value "16Mhz")
      (footprint "Thach Anh 2 chan cam")
      (description "Crystal For all Crystal 2pin.")
      (libsource (lib "Altium_Lib_by_KhueNguyenCreator") (part "Thach Anh 2 chan Cam"))
    )
  )
  (nets
    (net (code "1") (name "/3V3") (class "Default")
      (node (ref "AMS1") (pin "2") (pinfunction "VOUT_2") (pintype "passive"))
      (node (ref "AMS1") (pin "4") (pinfunction "VOUT_4") (pintype "passive"))
      (node (ref "C2") (pin "1") (pinfunction "1_1") (pintype "passive"))
      (node (ref "C3") (pin "1") (pinfunction "1_1") (pintype "passive"))
      (node (ref "C4") (pin "1") (pinfunction "1_1") (pintype "passive"))
      (node (ref "C5") (pin "1") (pinfunction "1_1") (pintype "passive"))
      (node (ref "C6") (pin "1") (pinfunction "1_1") (pintype "passive"))
      (node (ref "C7") (pin "1") (pinfunction "1_1") (pintype "passive"))
      (node (ref "H1") (pin "1") (pinfunction "1_1") (pintype "passive"))
      (node (ref "K1") (pin "3") (pinfunction "3_3") (pintype "passive"))
      (node (ref "R1") (pin "2") (pinfunction "2_2") (pintype "passive"))
      (node (ref "R11") (pin "1") (pinfunction "1_1") (pintype "passive"))
      (node (ref "R12") (pin "1") (pinfunction "1_1") (pintype "passive"))
      (node (ref "R16") (pin "1") (pinfunction "1_1") (pintype "passive"))
      (node (ref "R19") (pin "1") (pinfunction "1_1") (pintype "passive"))
      (node (ref "R20") (pin "1") (pinfunction "1_1") (pintype "passive"))
      (node (ref "R28") (pin "1") (pinfunction "1_1") (pintype "passive"))
      (node (ref "R32") (pin "1") (pinfunction "1_1") (pintype "passive"))
      (node (ref "R34") (pin "1") (pinfunction "1_1") (pintype "passive"))
      (node (ref "R41") (pin "1") (pinfunction "1_1") (pintype "passive"))
      (node (ref "R45") (pin "1") (pinfunction "1_1") (pintype "passive"))
      (node (ref "R51") (pin "1") (pinfunction "1_1") (pintype "passive"))
      (node (ref "R61") (pin "1") (pinfunction "1_1") (pintype "passive"))
      (node (ref "R71") (pin "1") (pinfunction "1_1") (pintype "passive"))
      (node (ref "R75") (pin "1") (pinfunction "1_1") (pintype "passive"))
      (node (ref "R8") (pin "2") (pinfunction "2_2") (pintype "passive"))
      (node (ref "U1") (pin "1") (pinfunction "VBAT_1") (pintype "passive"))
      (node (ref "U1") (pin "24") (pinfunction "VDD_1_24") (pintype "passive"))
      (node (ref "U1") (pin "36") (pinfunction "VDD_2_36") (pintype "passive"))
      (node (ref "U1") (pin "48") (pinfunction "VDD_3_48") (pintype "passive"))
      (node (ref "U1") (pin "9") (pinfunction "VDDA_9") (pintype "passive"))
    )
    (net (code "2") (name "/3v3R1") (class "Default")
      (node (ref "R11") (pin "2") (pinfunction "2_2") (pintype "passive"))
      (node (ref "U1") (pin "13") (pinfunction "PA3_13") (pintype "passive"))
      (node (ref "U2") (pin "4") (pinfunction "C_4") (pintype "passive"))
    )
    (net (code "3") (name "/3v3R2") (class "Default")
      (node (ref "R11") (pin "3") (pinfunction "3_3") (pintype "passive"))
      (node (ref "U1") (pin "14") (pinfunction "PA4_14") (pintype "passive"))
      (node (ref "U7") (pin "4") (pinfunction "C_4") (pintype "passive"))
    )
    (net (code "4") (name "/3v3R3") (class "Default")
      (node (ref "R11") (pin "4") (pinfunction "4_4") (pintype "passive"))
      (node (ref "U1") (pin "15") (pinfunction "PA5_15") (pintype "passive"))
      (node (ref "U12") (pin "4") (pinfunction "C_4") (pintype "passive"))
    )
    (net (code "5") (name "/3v3R4") (class "Default")
      (node (ref "R11") (pin "5") (pinfunction "5_5") (pintype "passive"))
      (node (ref "U1") (pin "16") (pinfunction "PA6_16") (pintype "passive"))
      (node (ref "U16") (pin "4") (pinfunction "C_4") (pintype "passive"))
    )
    (net (code "6") (name "/3v3R5") (class "Default")
      (node (ref "R11") (pin "6") (pinfunction "6_6") (pintype "passive"))
      (node (ref "U1") (pin "17") (pinfunction "PA7_17") (pintype "passive"))
      (node (ref "U20") (pin "4") (pinfunction "C_4") (pintype "passive"))
    )
    (net (code "7") (name "/3v3R6") (class "Default")
      (node (ref "R11") (pin "7") (pinfunction "7_7") (pintype "passive"))
      (node (ref "U1") (pin "18") (pinfunction "PB0_18") (pintype "passive"))
      (node (ref "U22") (pin "4") (pinfunction "C_4") (pintype "passive"))
    )
    (net (code "8") (name "/3v3R7") (class "Default")
      (node (ref "R11") (pin "8") (pinfunction "8_8") (pintype "passive"))
      (node (ref "U1") (pin "19") (pinfunction "PB1_19") (pintype "passive"))
      (node (ref "U26") (pin "4") (pinfunction "C_4") (pintype "passive"))
    )
    (net (code "9") (name "/3v3R8") (class "Default")
      (node (ref "R12") (pin "2") (pinfunction "2_2") (pintype "passive"))
      (node (ref "U1") (pin "20") (pinfunction "PB2_20") (pintype "passive"))
      (node (ref "U3") (pin "4") (pinfunction "C_4") (pintype "passive"))
    )
    (net (code "10") (name "/3v3R9") (class "Default")
      (node (ref "R12") (pin "3") (pinfunction "3_3") (pintype "passive"))
      (node (ref "U1") (pin "21") (pinfunction "PB10_21") (pintype "passive"))
      (node (ref "U8") (pin "4") (pinfunction "C_4") (pintype "passive"))
    )
    (net (code "11") (name "/3v3R10") (class "Default")
      (node (ref "R12") (pin "4") (pinfunction "4_4") (pintype "passive"))
      (node (ref "U1") (pin "22") (pinfunction "PB11_22") (pintype "passive"))
      (node (ref "U13") (pin "4") (pinfunction "C_4") (pintype "passive"))
    )
    (net (code "12") (name "/3v3R11") (class "Default")
      (node (ref "R12") (pin "5") (pinfunction "5_5") (pintype "passive"))
      (node (ref "U1") (pin "25") (pinfunction "PB12_25") (pintype "passive"))
      (node (ref "U17") (pin "4") (pinfunction "C_4") (pintype "passive"))
    )
    (net (code "13") (name "/3v3R12") (class "Default")
      (node (ref "R12") (pin "6") (pinfunction "6_6") (pintype "passive"))
      (node (ref "U1") (pin "26") (pinfunction "PB13_26") (pintype "passive"))
      (node (ref "U21") (pin "4") (pinfunction "C_4") (pintype "passive"))
    )
    (net (code "14") (name "/3v3R13") (class "Default")
      (node (ref "R12") (pin "7") (pinfunction "7_7") (pintype "passive"))
      (node (ref "U1") (pin "27") (pinfunction "PB14_27") (pintype "passive"))
      (node (ref "U23") (pin "4") (pinfunction "C_4") (pintype "passive"))
    )
    (net (code "15") (name "/3v3R14") (class "Default")
      (node (ref "R12") (pin "8") (pinfunction "8_8") (pintype "passive"))
      (node (ref "U1") (pin "28") (pinfunction "PB15_28") (pintype "passive"))
      (node (ref "U27") (pin "4") (pinfunction "C_4") (pintype "passive"))
    )
    (net (code "16") (name "/5V") (class "Default")
      (node (ref "AMS1") (pin "3") (pinfunction "VIN_3") (pintype "passive"))
      (node (ref "C1") (pin "1") (pinfunction "1_1") (pintype "passive"))
      (node (ref "K1") (pin "1") (pinfunction "1_1") (pintype "passive"))
      (node (ref "K3") (pin "3") (pinfunction "3_3") (pintype "passive"))
      (node (ref "R2") (pin "2") (pinfunction "2_2") (pintype "passive"))
      (node (ref "R4") (pin "2") (pinfunction "2_2") (pintype "passive"))
      (node (ref "R5") (pin "2") (pinfunction "2_2") (pintype "passive"))
    )
    (net (code "17") (name "/24V_IN") (class "Default")
      (node (ref "K10") (pin "1") (pinfunction "1_1") (pintype "passive"))
      (node (ref "K11") (pin "1") (pinfunction "1_1") (pintype "passive"))
      (node (ref "K12") (pin "1") (pinfunction "1_1") (pintype "passive"))
      (node (ref "K13") (pin "1") (pinfunction "1_1") (pintype "passive"))
      (node (ref "K14") (pin "1") (pinfunction "1_1") (pintype "passive"))
      (node (ref "K15") (pin "1") (pinfunction "1_1") (pintype "passive"))
      (node (ref "K16") (pin "1") (pinfunction "1_1") (pintype "passive"))
      (node (ref "K2") (pin "1") (pinfunction "1_1") (pintype "passive"))
    )
    (net (code "18") (name "/24V_OUT") (class "Default")
      (node (ref "K2") (pin "2") (pinfunction "2_2") (pintype "passive"))
      (node (ref "Q1") (pin "1") (pinfunction "E_1") (pintype "passive"))
      (node (ref "Q10") (pin "1") (pinfunction "E_1") (pintype "passive"))
      (node (ref "Q11") (pin "1") (pinfunction "E_1") (pintype "passive"))
      (node (ref "Q12") (pin "1") (pinfunction "E_1") (pintype "passive"))
      (node (ref "Q13") (pin "1") (pinfunction "E_1") (pintype "passive"))
      (node (ref "Q14") (pin "1") (pinfunction "E_1") (pintype "passive"))
      (node (ref "Q2") (pin "1") (pinfunction "E_1") (pintype "passive"))
      (node (ref "Q3") (pin "1") (pinfunction "E_1") (pintype "passive"))
      (node (ref "Q4") (pin "1") (pinfunction "E_1") (pintype "passive"))
      (node (ref "Q5") (pin "1") (pinfunction "E_1") (pintype "passive"))
      (node (ref "Q6") (pin "1") (pinfunction "E_1") (pintype "passive"))
      (node (ref "Q7") (pin "1") (pinfunction "E_1") (pintype "passive"))
      (node (ref "Q8") (pin "1") (pinfunction "E_1") (pintype "passive"))
      (node (ref "Q9") (pin "1") (pinfunction "E_1") (pintype "passive"))
      (node (ref "R10") (pin "2") (pinfunction "2_2") (pintype "passive"))
      (node (ref "R13") (pin "2") (pinfunction "2_2") (pintype "passive"))
      (node (ref "R25") (pin "2") (pinfunction "2_2") (pintype "passive"))
      (node (ref "R26") (pin "2") (pinfunction "2_2") (pintype "passive"))
      (node (ref "R27") (pin "2") (pinfunction "2_2") (pintype "passive"))
      (node (ref "R39") (pin "2") (pinfunction "2_2") (pintype "passive"))
      (node (ref "R40") (pin "2") (pinfunction "2_2") (pintype "passive"))
      (node (ref "R49") (pin "2") (pinfunction "2_2") (pintype "passive"))
      (node (ref "R50") (pin "2") (pinfunction "2_2") (pintype "passive"))
      (node (ref "R59") (pin "2") (pinfunction "2_2") (pintype "passive"))
      (node (ref "R60") (pin "2") (pinfunction "2_2") (pintype "passive"))
      (node (ref "R69") (pin "2") (pinfunction "2_2") (pintype "passive"))
      (node (ref "R70") (pin "2") (pinfunction "2_2") (pintype "passive"))
      (node (ref "R9") (pin "2") (pinfunction "2_2") (pintype "passive"))
    )
    (net (code "19") (name "/A") (class "Default")
      (node (ref "C11") (pin "1") (pinfunction "1_1") (pintype "passive"))
      (node (ref "K3") (pin "1") (pinfunction "1_1") (pintype "passive"))
      (node (ref "R4") (pin "1") (pinfunction "1_1") (pintype "passive"))
      (node (ref "R6") (pin "2") (pinfunction "2_2") (pintype "passive"))
    )
    (net (code "20") (name "/B") (class "Default")
      (node (ref "C10") (pin "1") (pinfunction "1_1") (pintype "passive"))
      (node (ref "K3") (pin "2") (pinfunction "2_2") (pintype "passive"))
      (node (ref "R5") (pin "1") (pinfunction "1_1") (pintype "passive"))
      (node (ref "R7") (pin "2") (pinfunction "2_2") (pintype "passive"))
    )
    (net (code "21") (name "/EN_A") (class "Default")
      (node (ref "R6") (pin "1") (pinfunction "1_1") (pintype "passive"))
      (node (ref "U1") (pin "11") (pinfunction "PA1_11") (pintype "passive"))
    )
    (net (code "22") (name "/EN_B") (class "Default")
      (node (ref "R7") (pin "1") (pinfunction "1_1") (pintype "passive"))
      (node (ref "U1") (pin "12") (pinfunction "PA2_12") (pintype "passive"))
    )
    (net (code "23") (name "/IN1") (class "Default")
      (node (ref "K10") (pin "4") (pinfunction "4_4") (pintype "passive"))
      (node (ref "R14") (pin "1") (pinfunction "1_1") (pintype "passive"))
    )
    (net (code "24") (name "/IN2") (class "Default")
      (node (ref "K10") (pin "3") (pinfunction "3_3") (pintype "passive"))
      (node (ref "R29") (pin "1") (pinfunction "1_1") (pintype "passive"))
    )
    (net (code "25") (name "/IN3") (class "Default")
      (node (ref "K11") (pin "4") (pinfunction "4_4") (pintype "passive"))
      (node (ref "R43") (pin "1") (pinfunction "1_1") (pintype "passive"))
    )
    (net (code "26") (name "/IN4") (class "Default")
      (node (ref "K11") (pin "3") (pinfunction "3_3") (pintype "passive"))
      (node (ref "R55") (pin "1") (pinfunction "1_1") (pintype "passive"))
    )
    (net (code "27") (name "/IN5") (class "Default")
      (node (ref "K12") (pin "4") (pinfunction "4_4") (pintype "passive"))
      (node (ref "R65") (pin "1") (pinfunction "1_1") (pintype "passive"))
    )
    (net (code "28") (name "/IN6") (class "Default")
      (node (ref "K12") (pin "3") (pinfunction "3_3") (pintype "passive"))
      (node (ref "R73") (pin "1") (pinfunction "1_1") (pintype "passive"))
    )
    (net (code "29") (name "/IN7") (class "Default")
      (node (ref "K13") (pin "4") (pinfunction "4_4") (pintype "passive"))
      (node (ref "R83") (pin "1") (pinfunction "1_1") (pintype "passive"))
    )
    (net (code "30") (name "/IN8") (class "Default")
      (node (ref "K13") (pin "3") (pinfunction "3_3") (pintype "passive"))
      (node (ref "R15") (pin "1") (pinfunction "1_1") (pintype "passive"))
    )
    (net (code "31") (name "/IN9") (class "Default")
      (node (ref "K14") (pin "4") (pinfunction "4_4") (pintype "passive"))
      (node (ref "R30") (pin "1") (pinfunction "1_1") (pintype "passive"))
    )
    (net (code "32") (name "/IN10") (class "Default")
      (node (ref "K14") (pin "3") (pinfunction "3_3") (pintype "passive"))
      (node (ref "R44") (pin "1") (pinfunction "1_1") (pintype "passive"))
    )
    (net (code "33") (name "/IN11") (class "Default")
      (node (ref "K15") (pin "4") (pinfunction "4_4") (pintype "passive"))
      (node (ref "R56") (pin "1") (pinfunction "1_1") (pintype "passive"))
    )
    (net (code "34") (name "/IN12") (class "Default")
      (node (ref "K15") (pin "3") (pinfunction "3_3") (pintype "passive"))
      (node (ref "R66") (pin "1") (pinfunction "1_1") (pintype "passive"))
    )
    (net (code "35") (name "/IN13") (class "Default")
      (node (ref "K16") (pin "4") (pinfunction "4_4") (pintype "passive"))
      (node (ref "R74") (pin "1") (pinfunction "1_1") (pintype "passive"))
    )
    (net (code "36") (name "/IN14") (class "Default")
      (node (ref "K16") (pin "3") (pinfunction "3_3") (pintype "passive"))
      (node (ref "R84") (pin "1") (pinfunction "1_1") (pintype "passive"))
    )
    (net (code "37") (name "/OUT1") (class "Default")
      (node (ref "DIO1") (pin "2") (pinfunction "K_2") (pintype "passive"))
      (node (ref "K4") (pin "3") (pinfunction "3_3") (pintype "passive"))
      (node (ref "Q1") (pin "2") (pinfunction "C_2") (pintype "passive"))
      (node (ref "R22") (pin "2") (pinfunction "2_2") (pintype "passive"))
    )
    (net (code "38") (name "/OUT2") (class "Default")
      (node (ref "DIO5") (pin "2") (pinfunction "K_2") (pintype "passive"))
      (node (ref "K4") (pin "4") (pinfunction "4_4") (pintype "passive"))
      (node (ref "Q5") (pin "2") (pinfunction "C_2") (pintype "passive"))
      (node (ref "R37") (pin "2") (pinfunction "2_2") (pintype "passive"))
    )
    (net (code "39") (name "/OUT3") (class "Default")
      (node (ref "DIO7") (pin "2") (pinfunction "K_2") (pintype "passive"))
      (node (ref "K5") (pin "3") (pinfunction "3_3") (pintype "passive"))
      (node (ref "Q7") (pin "2") (pinfunction "C_2") (pintype "passive"))
      (node (ref "R47") (pin "2") (pinfunction "2_2") (pintype "passive"))
    )
    (net (code "40") (name "/OUT4") (class "Default")
      (node (ref "DIO9") (pin "2") (pinfunction "K_2") (pintype "passive"))
      (node (ref "K5") (pin "4") (pinfunction "4_4") (pintype "passive"))
      (node (ref "Q9") (pin "2") (pinfunction "C_2") (pintype "passive"))
      (node (ref "R57") (pin "2") (pinfunction "2_2") (pintype "passive"))
    )
    (net (code "41") (name "/OUT5") (class "Default")
      (node (ref "DIO11") (pin "2") (pinfunction "K_2") (pintype "passive"))
      (node (ref "K6") (pin "3") (pinfunction "3_3") (pintype "passive"))
      (node (ref "Q11") (pin "2") (pinfunction "C_2") (pintype "passive"))
      (node (ref "R67") (pin "2") (pinfunction "2_2") (pintype "passive"))
    )
    (net (code "42") (name "/OUT6") (class "Default")
      (node (ref "DIO13") (pin "2") (pinfunction "K_2") (pintype "passive"))
      (node (ref "K6") (pin "4") (pinfunction "4_4") (pintype "passive"))
      (node (ref "Q13") (pin "2") (pinfunction "C_2") (pintype "passive"))
      (node (ref "R77") (pin "2") (pinfunction "2_2") (pintype "passive"))
    )
    (net (code "43") (name "/OUT7") (class "Default")
      (node (ref "DIO3") (pin "2") (pinfunction "K_2") (pintype "passive"))
      (node (ref "K7") (pin "3") (pinfunction "3_3") (pintype "passive"))
      (node (ref "Q3") (pin "2") (pinfunction "C_2") (pintype "passive"))
      (node (ref "R24") (pin "2") (pinfunction "2_2") (pintype "passive"))
    )
    (net (code "44") (name "/OUT8") (class "Default")
      (node (ref "DIO6") (pin "2") (pinfunction "K_2") (pintype "passive"))
      (node (ref "K7") (pin "4") (pinfunction "4_4") (pintype "passive"))
      (node (ref "Q6") (pin "2") (pinfunction "C_2") (pintype "passive"))
      (node (ref "R38") (pin "2") (pinfunction "2_2") (pintype "passive"))
    )
    (net (code "45") (name "/OUT9") (class "Default")
      (node (ref "DIO8") (pin "2") (pinfunction "K_2") (pintype "passive"))
      (node (ref "K8") (pin "3") (pinfunction "3_3") (pintype "passive"))
      (node (ref "Q8") (pin "2") (pinfunction "C_2") (pintype "passive"))
      (node (ref "R48") (pin "2") (pinfunction "2_2") (pintype "passive"))
    )
    (net (code "46") (name "/OUT10") (class "Default")
      (node (ref "DIO10") (pin "2") (pinfunction "K_2") (pintype "passive"))
      (node (ref "K8") (pin "4") (pinfunction "4_4") (pintype "passive"))
      (node (ref "Q10") (pin "2") (pinfunction "C_2") (pintype "passive"))
      (node (ref "R58") (pin "2") (pinfunction "2_2") (pintype "passive"))
    )
    (net (code "47") (name "/OUT11") (class "Default")
      (node (ref "DIO12") (pin "2") (pinfunction "K_2") (pintype "passive"))
      (node (ref "K9") (pin "3") (pinfunction "3_3") (pintype "passive"))
      (node (ref "Q12") (pin "2") (pinfunction "C_2") (pintype "passive"))
      (node (ref "R68") (pin "2") (pinfunction "2_2") (pintype "passive"))
    )
    (net (code "48") (name "/OUT12") (class "Default")
      (node (ref "DIO14") (pin "2") (pinfunction "K_2") (pintype "passive"))
      (node (ref "K9") (pin "4") (pinfunction "4_4") (pintype "passive"))
      (node (ref "Q14") (pin "2") (pinfunction "C_2") (pintype "passive"))
      (node (ref "R78") (pin "2") (pinfunction "2_2") (pintype "passive"))
    )
    (net (code "49") (name "/OUT13") (class "Default")
      (node (ref "DIO2") (pin "2") (pinfunction "K_2") (pintype "passive"))
      (node (ref "K17") (pin "3") (pinfunction "3_3") (pintype "passive"))
      (node (ref "Q2") (pin "2") (pinfunction "C_2") (pintype "passive"))
      (node (ref "R23") (pin "2") (pinfunction "2_2") (pintype "passive"))
    )
    (net (code "50") (name "/OUT14") (class "Default")
      (node (ref "DIO4") (pin "2") (pinfunction "K_2") (pintype "passive"))
      (node (ref "K17") (pin "4") (pinfunction "4_4") (pintype "passive"))
      (node (ref "Q4") (pin "2") (pinfunction "C_2") (pintype "passive"))
      (node (ref "R36") (pin "2") (pinfunction "2_2") (pintype "passive"))
    )
    (net (code "51") (name "/SWCLK") (class "Default")
      (node (ref "H1") (pin "2") (pinfunction "2_2") (pintype "passive"))
      (node (ref "U1") (pin "37") (pinfunction "PA14_37") (pintype "passive"))
    )
    (net (code "52") (name "/SWDIO") (class "Default")
      (node (ref "H1") (pin "3") (pinfunction "3_3") (pintype "passive"))
      (node (ref "U1") (pin "34") (pinfunction "PA13_34") (pintype "passive"))
    )
    (net (code "53") (name "/st_out1") (class "Default")
      (node (ref "U1") (pin "31") (pinfunction "PA10_31") (pintype "passive"))
      (node (ref "U4") (pin "2") (pinfunction "K_2") (pintype "passive"))
    )
    (net (code "54") (name "/st_out2") (class "Default")
      (node (ref "U1") (pin "32") (pinfunction "PA11_32") (pintype "passive"))
      (node (ref "U10") (pin "2") (pinfunction "K_2") (pintype "passive"))
    )
    (net (code "55") (name "/st_out3") (class "Default")
      (node (ref "U1") (pin "33") (pinfunction "PA12_33") (pintype "passive"))
      (node (ref "U14") (pin "2") (pinfunction "K_2") (pintype "passive"))
    )
    (net (code "56") (name "/st_out4") (class "Default")
      (node (ref "U1") (pin "38") (pinfunction "PA15_38") (pintype "passive"))
      (node (ref "U18") (pin "2") (pinfunction "K_2") (pintype "passive"))
    )
    (net (code "57") (name "/st_out5") (class "Default")
      (node (ref "U1") (pin "39") (pinfunction "PB3_39") (pintype "passive"))
      (node (ref "U24") (pin "2") (pinfunction "K_2") (pintype "passive"))
    )
    (net (code "58") (name "/st_out6") (class "Default")
      (node (ref "U1") (pin "40") (pinfunction "PB4_40") (pintype "passive"))
      (node (ref "U28") (pin "2") (pinfunction "K_2") (pintype "passive"))
    )
    (net (code "59") (name "/st_out7") (class "Default")
      (node (ref "U1") (pin "41") (pinfunction "PB5_41") (pintype "passive"))
      (node (ref "U6") (pin "2") (pinfunction "K_2") (pintype "passive"))
    )
    (net (code "60") (name "/st_out8") (class "Default")
      (node (ref "U1") (pin "42") (pinfunction "PB6_42") (pintype "passive"))
      (node (ref "U11") (pin "2") (pinfunction "K_2") (pintype "passive"))
    )
    (net (code "61") (name "/st_out9") (class "Default")
      (node (ref "U1") (pin "43") (pinfunction "PB7_43") (pintype "passive"))
      (node (ref "U15") (pin "2") (pinfunction "K_2") (pintype "passive"))
    )
    (net (code "62") (name "/st_out10") (class "Default")
      (node (ref "U1") (pin "45") (pinfunction "PB8_45") (pintype "passive"))
      (node (ref "U19") (pin "2") (pinfunction "K_2") (pintype "passive"))
    )
    (net (code "63") (name "/st_out11") (class "Default")
      (node (ref "U1") (pin "46") (pinfunction "PB9_46") (pintype "passive"))
      (node (ref "U25") (pin "2") (pinfunction "K_2") (pintype "passive"))
    )
    (net (code "64") (name "/st_out12") (class "Default")
      (node (ref "U1") (pin "2") (pinfunction "PC13-TAMPER-RT_C_2") (pintype "passive"))
      (node (ref "U29") (pin "2") (pinfunction "K_2") (pintype "passive"))
    )
    (net (code "65") (name "/st_out13") (class "Default")
      (node (ref "U1") (pin "3") (pinfunction "PC14-OSC32_IN_3") (pintype "passive"))
      (node (ref "U5") (pin "2") (pinfunction "K_2") (pintype "passive"))
    )
    (net (code "66") (name "/st_out14") (class "Default")
      (node (ref "U1") (pin "4") (pinfunction "PC15-OSC32_OUT_4") (pintype "passive"))
      (node (ref "U9") (pin "2") (pinfunction "K_2") (pintype "passive"))
    )
    (net (code "67") (name "GND_24") (class "Default")
      (node (ref "DIO1") (pin "1") (pinfunction "A_1") (pintype "passive"))
      (node (ref "DIO10") (pin "1") (pinfunction "A_1") (pintype "passive"))
      (node (ref "DIO11") (pin "1") (pinfunction "A_1") (pintype "passive"))
      (node (ref "DIO12") (pin "1") (pinfunction "A_1") (pintype "passive"))
      (node (ref "DIO13") (pin "1") (pinfunction "A_1") (pintype "passive"))
      (node (ref "DIO14") (pin "1") (pinfunction "A_1") (pintype "passive"))
      (node (ref "DIO2") (pin "1") (pinfunction "A_1") (pintype "passive"))
      (node (ref "DIO3") (pin "1") (pinfunction "A_1") (pintype "passive"))
      (node (ref "DIO4") (pin "1") (pinfunction "A_1") (pintype "passive"))
      (node (ref "DIO5") (pin "1") (pinfunction "A_1") (pintype "passive"))
      (node (ref "DIO6") (pin "1") (pinfunction "A_1") (pintype "passive"))
      (node (ref "DIO7") (pin "1") (pinfunction "A_1") (pintype "passive"))
      (node (ref "DIO8") (pin "1") (pinfunction "A_1") (pintype "passive"))
      (node (ref "DIO9") (pin "1") (pinfunction "A_1") (pintype "passive"))
      (node (ref "K10") (pin "2") (pinfunction "2_2") (pintype "passive"))
      (node (ref "K11") (pin "2") (pinfunction "2_2") (pintype "passive"))
      (node (ref "K12") (pin "2") (pinfunction "2_2") (pintype "passive"))
      (node (ref "K13") (pin "2") (pinfunction "2_2") (pintype "passive"))
      (node (ref "K14") (pin "2") (pinfunction "2_2") (pintype "passive"))
      (node (ref "K15") (pin "2") (pinfunction "2_2") (pintype "passive"))
      (node (ref "K16") (pin "2") (pinfunction "2_2") (pintype "passive"))
      (node (ref "K17") (pin "1") (pinfunction "1_1") (pintype "passive"))
      (node (ref "K17") (pin "2") (pinfunction "2_2") (pintype "passive"))
      (node (ref "K2") (pin "3") (pinfunction "3_3") (pintype "passive"))
      (node (ref "K2") (pin "4") (pinfunction "4_4") (pintype "passive"))
      (node (ref "K4") (pin "1") (pinfunction "1_1") (pintype "passive"))
      (node (ref "K4") (pin "2") (pinfunction "2_2") (pintype "passive"))
      (node (ref "K5") (pin "1") (pinfunction "1_1") (pintype "passive"))
      (node (ref "K5") (pin "2") (pinfunction "2_2") (pintype "passive"))
      (node (ref "K6") (pin "1") (pinfunction "1_1") (pintype "passive"))
      (node (ref "K6") (pin "2") (pinfunction "2_2") (pintype "passive"))
      (node (ref "K7") (pin "1") (pinfunction "1_1") (pintype "passive"))
      (node (ref "K7") (pin "2") (pinfunction "2_2") (pintype "passive"))
      (node (ref "K8") (pin "1") (pinfunction "1_1") (pintype "passive"))
      (node (ref "K8") (pin "2") (pinfunction "2_2") (pintype "passive"))
      (node (ref "K9") (pin "1") (pinfunction "1_1") (pintype "passive"))
      (node (ref "K9") (pin "2") (pinfunction "2_2") (pintype "passive"))
      (node (ref "L10") (pin "2") (pinfunction "K_2") (pintype "passive"))
      (node (ref "L11") (pin "2") (pinfunction "K_2") (pintype "passive"))
      (node (ref "L12") (pin "2") (pinfunction "K_2") (pintype "passive"))
      (node (ref "L17") (pin "2") (pinfunction "K_2") (pintype "passive"))
      (node (ref "L18") (pin "2") (pinfunction "K_2") (pintype "passive"))
      (node (ref "L21") (pin "2") (pinfunction "K_2") (pintype "passive"))
      (node (ref "L22") (pin "2") (pinfunction "K_2") (pintype "passive"))
      (node (ref "L25") (pin "2") (pinfunction "K_2") (pintype "passive"))
      (node (ref "L26") (pin "2") (pinfunction "K_2") (pintype "passive"))
      (node (ref "L29") (pin "2") (pinfunction "K_2") (pintype "passive"))
      (node (ref "L30") (pin "2") (pinfunction "K_2") (pintype "passive"))
      (node (ref "L5") (pin "2") (pinfunction "K_2") (pintype "passive"))
      (node (ref "L6") (pin "2") (pinfunction "K_2") (pintype "passive"))
      (node (ref "L7") (pin "2") (pinfunction "K_2") (pintype "passive"))
      (node (ref "U10") (pin "3") (pinfunction "E_3") (pintype "passive"))
      (node (ref "U11") (pin "3") (pinfunction "E_3") (pintype "passive"))
      (node (ref "U12") (pin "2") (pinfunction "K_2") (pintype "passive"))
      (node (ref "U13") (pin "2") (pinfunction "K_2") (pintype "passive"))
      (node (ref "U14") (pin "3") (pinfunction "E_3") (pintype "passive"))
      (node (ref "U15") (pin "3") (pinfunction "E_3") (pintype "passive"))
      (node (ref "U16") (pin "2") (pinfunction "K_2") (pintype "passive"))
      (node (ref "U17") (pin "2") (pinfunction "K_2") (pintype "passive"))
      (node (ref "U18") (pin "3") (pinfunction "E_3") (pintype "passive"))
      (node (ref "U19") (pin "3") (pinfunction "E_3") (pintype "passive"))
      (node (ref "U2") (pin "2") (pinfunction "K_2") (pintype "passive"))
      (node (ref "U20") (pin "2") (pinfunction "K_2") (pintype "passive"))
      (node (ref "U21") (pin "2") (pinfunction "K_2") (pintype "passive"))
      (node (ref "U22") (pin "2") (pinfunction "K_2") (pintype "passive"))
      (node (ref "U23") (pin "2") (pinfunction "K_2") (pintype "passive"))
      (node (ref "U24") (pin "3") (pinfunction "E_3") (pintype "passive"))
      (node (ref "U25") (pin "3") (pinfunction "E_3") (pintype "passive"))
      (node (ref "U26") (pin "2") (pinfunction "K_2") (pintype "passive"))
      (node (ref "U27") (pin "2") (pinfunction "K_2") (pintype "passive"))
      (node (ref "U28") (pin "3") (pinfunction "E_3") (pintype "passive"))
      (node (ref "U29") (pin "3") (pinfunction "E_3") (pintype "passive"))
      (node (ref "U3") (pin "2") (pinfunction "K_2") (pintype "passive"))
      (node (ref "U4") (pin "3") (pinfunction "E_3") (pintype "passive"))
      (node (ref "U5") (pin "3") (pinfunction "E_3") (pintype "passive"))
      (node (ref "U6") (pin "3") (pinfunction "E_3") (pintype "passive"))
      (node (ref "U7") (pin "2") (pinfunction "K_2") (pintype "passive"))
      (node (ref "U8") (pin "2") (pinfunction "K_2") (pintype "passive"))
      (node (ref "U9") (pin "3") (pinfunction "E_3") (pintype "passive"))
    )
    (net (code "68") (name "GND_33") (class "Default")
      (node (ref "AMS1") (pin "1") (pinfunction "GND_1") (pintype "passive"))
      (node (ref "BT1") (pin "1") (pinfunction "1_1") (pintype "passive"))
      (node (ref "C1") (pin "2") (pinfunction "2_2") (pintype "passive"))
      (node (ref "C10") (pin "2") (pinfunction "2_2") (pintype "passive"))
      (node (ref "C11") (pin "2") (pinfunction "2_2") (pintype "passive"))
      (node (ref "C12") (pin "2") (pinfunction "2_2") (pintype "passive"))
      (node (ref "C2") (pin "2") (pinfunction "2_2") (pintype "passive"))
      (node (ref "C3") (pin "2") (pinfunction "2_2") (pintype "passive"))
      (node (ref "C4") (pin "2") (pinfunction "2_2") (pintype "passive"))
      (node (ref "C5") (pin "2") (pinfunction "2_2") (pintype "passive"))
      (node (ref "C6") (pin "2") (pinfunction "2_2") (pintype "passive"))
      (node (ref "C7") (pin "2") (pinfunction "2_2") (pintype "passive"))
      (node (ref "C8") (pin "2") (pinfunction "2_2") (pintype "passive"))
      (node (ref "C9") (pin "2") (pinfunction "2_2") (pintype "passive"))
      (node (ref "H1") (pin "4") (pinfunction "4_4") (pintype "passive"))
      (node (ref "K1") (pin "2") (pinfunction "2_2") (pintype "passive"))
      (node (ref "K1") (pin "4") (pinfunction "4_4") (pintype "passive"))
      (node (ref "K3") (pin "4") (pinfunction "4_4") (pintype "passive"))
      (node (ref "L1") (pin "2") (pinfunction "K_2") (pintype "passive"))
      (node (ref "L2") (pin "2") (pinfunction "K_2") (pintype "passive"))
      (node (ref "R3") (pin "2") (pinfunction "2_2") (pintype "passive"))
      (node (ref "U1") (pin "23") (pinfunction "VSS_1_23") (pintype "passive"))
      (node (ref "U1") (pin "35") (pinfunction "VSS_2_35") (pintype "passive"))
      (node (ref "U1") (pin "47") (pinfunction "VSS_3_47") (pintype "passive"))
      (node (ref "U1") (pin "8") (pinfunction "VSSA_8") (pintype "passive"))
      (node (ref "U12") (pin "3") (pinfunction "E_3") (pintype "passive"))
      (node (ref "U13") (pin "3") (pinfunction "E_3") (pintype "passive"))
      (node (ref "U16") (pin "3") (pinfunction "E_3") (pintype "passive"))
      (node (ref "U17") (pin "3") (pinfunction "E_3") (pintype "passive"))
      (node (ref "U2") (pin "3") (pinfunction "E_3") (pintype "passive"))
      (node (ref "U20") (pin "3") (pinfunction "E_3") (pintype "passive"))
      (node (ref "U21") (pin "3") (pinfunction "E_3") (pintype "passive"))
      (node (ref "U22") (pin "3") (pinfunction "E_3") (pintype "passive"))
      (node (ref "U23") (pin "3") (pinfunction "E_3") (pintype "passive"))
      (node (ref "U26") (pin "3") (pinfunction "E_3") (pintype "passive"))
      (node (ref "U27") (pin "3") (pinfunction "E_3") (pintype "passive"))
      (node (ref "U3") (pin "3") (pinfunction "E_3") (pintype "passive"))
      (node (ref "U7") (pin "3") (pinfunction "E_3") (pintype "passive"))
      (node (ref "U8") (pin "3") (pinfunction "E_3") (pintype "passive"))
    )
    (net (code "69") (name "Net-(L1-A)") (class "Default")
      (node (ref "L1") (pin "1") (pinfunction "A_1") (pintype "passive"))
      (node (ref "R1") (pin "1") (pinfunction "1_1") (pintype "passive"))
    )
    (net (code "70") (name "Net-(L2-A)") (class "Default")
      (node (ref "L2") (pin "1") (pinfunction "A_1") (pintype "passive"))
      (node (ref "R2") (pin "1") (pinfunction "1_1") (pintype "passive"))
    )
    (net (code "71") (name "Net-(L3-A)") (class "Default")
      (node (ref "L3") (pin "1") (pinfunction "A_1") (pintype "passive"))
      (node (ref "R14") (pin "2") (pinfunction "2_2") (pintype "passive"))
    )
    (net (code "72") (name "Net-(L3-K)") (class "Default")
      (node (ref "L3") (pin "2") (pinfunction "K_2") (pintype "passive"))
      (node (ref "U2") (pin "1") (pinfunction "A_1") (pintype "passive"))
    )
    (net (code "73") (name "Net-(L4-A)") (class "Default")
      (node (ref "L4") (pin "1") (pinfunction "A_1") (pintype "passive"))
      (node (ref "R15") (pin "2") (pinfunction "2_2") (pintype "passive"))
    )
    (net (code "74") (name "Net-(L4-K)") (class "Default")
      (node (ref "L4") (pin "2") (pinfunction "K_2") (pintype "passive"))
      (node (ref "U3") (pin "1") (pinfunction "A_1") (pintype "passive"))
    )
    (net (code "75") (name "Net-(L5-A)") (class "Default")
      (node (ref "L5") (pin "1") (pinfunction "A_1") (pintype "passive"))
      (node (ref "R23") (pin "1") (pinfunction "1_1") (pintype "passive"))
    )
    (net (code "76") (name "Net-(L6-A)") (class "Default")
      (node (ref "L6") (pin "1") (pinfunction "A_1") (pintype "passive"))
      (node (ref "R22") (pin "1") (pinfunction "1_1") (pintype "passive"))
    )
    (net (code "77") (name "Net-(L7-A)") (class "Default")
      (node (ref "L7") (pin "1") (pinfunction "A_1") (pintype "passive"))
      (node (ref "R24") (pin "1") (pinfunction "1_1") (pintype "passive"))
    )
    (net (code "78") (name "Net-(L8-A)") (class "Default")
      (node (ref "L8") (pin "1") (pinfunction "A_1") (pintype "passive"))
      (node (ref "R29") (pin "2") (pinfunction "2_2") (pintype "passive"))
    )
    (net (code "79") (name "Net-(L8-K)") (class "Default")
      (node (ref "L8") (pin "2") (pinfunction "K_2") (pintype "passive"))
      (node (ref "U7") (pin "1") (pinfunction "A_1") (pintype "passive"))
    )
    (net (code "80") (name "Net-(L9-A)") (class "Default")
      (node (ref "L9") (pin "1") (pinfunction "A_1") (pintype "passive"))
      (node (ref "R30") (pin "2") (pinfunction "2_2") (pintype "passive"))
    )
    (net (code "81") (name "Net-(L9-K)") (class "Default")
      (node (ref "L9") (pin "2") (pinfunction "K_2") (pintype "passive"))
      (node (ref "U8") (pin "1") (pinfunction "A_1") (pintype "passive"))
    )
    (net (code "82") (name "Net-(L13-A)") (class "Default")
      (node (ref "L13") (pin "1") (pinfunction "A_1") (pintype "passive"))
      (node (ref "R43") (pin "2") (pinfunction "2_2") (pintype "passive"))
    )
    (net (code "83") (name "Net-(L13-K)") (class "Default")
      (node (ref "L13") (pin "2") (pinfunction "K_2") (pintype "passive"))
      (node (ref "U12") (pin "1") (pinfunction "A_1") (pintype "passive"))
    )
    (net (code "84") (name "Net-(L14-A)") (class "Default")
      (node (ref "L14") (pin "1") (pinfunction "A_1") (pintype "passive"))
      (node (ref "R44") (pin "2") (pinfunction "2_2") (pintype "passive"))
    )
    (net (code "85") (name "Net-(L14-K)") (class "Default")
      (node (ref "L14") (pin "2") (pinfunction "K_2") (pintype "passive"))
      (node (ref "U13") (pin "1") (pinfunction "A_1") (pintype "passive"))
    )
    (net (code "86") (name "Net-(L15-A)") (class "Default")
      (node (ref "L15") (pin "1") (pinfunction "A_1") (pintype "passive"))
      (node (ref "R55") (pin "2") (pinfunction "2_2") (pintype "passive"))
    )
    (net (code "87") (name "Net-(L15-K)") (class "Default")
      (node (ref "L15") (pin "2") (pinfunction "K_2") (pintype "passive"))
      (node (ref "U16") (pin "1") (pinfunction "A_1") (pintype "passive"))
    )
    (net (code "88") (name "Net-(L16-A)") (class "Default")
      (node (ref "L16") (pin "1") (pinfunction "A_1") (pintype "passive"))
      (node (ref "R56") (pin "2") (pinfunction "2_2") (pintype "passive"))
    )
    (net (code "89") (name "Net-(L16-K)") (class "Default")
      (node (ref "L16") (pin "2") (pinfunction "K_2") (pintype "passive"))
      (node (ref "U17") (pin "1") (pinfunction "A_1") (pintype "passive"))
    )
    (net (code "90") (name "Net-(L17-A)") (class "Default")
      (node (ref "L17") (pin "1") (pinfunction "A_1") (pintype "passive"))
      (node (ref "R47") (pin "1") (pinfunction "1_1") (pintype "passive"))
    )
    (net (code "91") (name "Net-(L18-A)") (class "Default")
      (node (ref "L18") (pin "1") (pinfunction "A_1") (pintype "passive"))
      (node (ref "R48") (pin "1") (pinfunction "1_1") (pintype "passive"))
    )
    (net (code "92") (name "Net-(L19-A)") (class "Default")
      (node (ref "L19") (pin "1") (pinfunction "A_1") (pintype "passive"))
      (node (ref "R65") (pin "2") (pinfunction "2_2") (pintype "passive"))
    )
    (net (code "93") (name "Net-(L19-K)") (class "Default")
      (node (ref "L19") (pin "2") (pinfunction "K_2") (pintype "passive"))
      (node (ref "U20") (pin "1") (pinfunction "A_1") (pintype "passive"))
    )
    (net (code "94") (name "Net-(L20-A)") (class "Default")
      (node (ref "L20") (pin "1") (pinfunction "A_1") (pintype "passive"))
      (node (ref "R66") (pin "2") (pinfunction "2_2") (pintype "passive"))
    )
    (net (code "95") (name "Net-(L20-K)") (class "Default")
      (node (ref "L20") (pin "2") (pinfunction "K_2") (pintype "passive"))
      (node (ref "U21") (pin "1") (pinfunction "A_1") (pintype "passive"))
    )
    (net (code "96") (name "Net-(L21-A)") (class "Default")
      (node (ref "L21") (pin "1") (pinfunction "A_1") (pintype "passive"))
      (node (ref "R57") (pin "1") (pinfunction "1_1") (pintype "passive"))
    )
    (net (code "97") (name "Net-(L22-A)") (class "Default")
      (node (ref "L22") (pin "1") (pinfunction "A_1") (pintype "passive"))
      (node (ref "R58") (pin "1") (pinfunction "1_1") (pintype "passive"))
    )
    (net (code "98") (name "Net-(L23-A)") (class "Default")
      (node (ref "L23") (pin "1") (pinfunction "A_1") (pintype "passive"))
      (node (ref "R73") (pin "2") (pinfunction "2_2") (pintype "passive"))
    )
    (net (code "99") (name "Net-(L23-K)") (class "Default")
      (node (ref "L23") (pin "2") (pinfunction "K_2") (pintype "passive"))
      (node (ref "U22") (pin "1") (pinfunction "A_1") (pintype "passive"))
    )
    (net (code "100") (name "Net-(L24-A)") (class "Default")
      (node (ref "L24") (pin "1") (pinfunction "A_1") (pintype "passive"))
      (node (ref "R74") (pin "2") (pinfunction "2_2") (pintype "passive"))
    )
    (net (code "101") (name "Net-(L24-K)") (class "Default")
      (node (ref "L24") (pin "2") (pinfunction "K_2") (pintype "passive"))
      (node (ref "U23") (pin "1") (pinfunction "A_1") (pintype "passive"))
    )
    (net (code "102") (name "Net-(L25-A)") (class "Default")
      (node (ref "L25") (pin "1") (pinfunction "A_1") (pintype "passive"))
      (node (ref "R67") (pin "1") (pinfunction "1_1") (pintype "passive"))
    )
    (net (code "103") (name "Net-(L26-A)") (class "Default")
      (node (ref "L26") (pin "1") (pinfunction "A_1") (pintype "passive"))
      (node (ref "R68") (pin "1") (pinfunction "1_1") (pintype "passive"))
    )
    (net (code "104") (name "Net-(L27-A)") (class "Default")
      (node (ref "L27") (pin "1") (pinfunction "A_1") (pintype "passive"))
      (node (ref "R83") (pin "2") (pinfunction "2_2") (pintype "passive"))
    )
    (net (code "105") (name "Net-(L27-K)") (class "Default")
      (node (ref "L27") (pin "2") (pinfunction "K_2") (pintype "passive"))
      (node (ref "U26") (pin "1") (pinfunction "A_1") (pintype "passive"))
    )
    (net (code "106") (name "Net-(L28-A)") (class "Default")
      (node (ref "L28") (pin "1") (pinfunction "A_1") (pintype "passive"))
      (node (ref "R84") (pin "2") (pinfunction "2_2") (pintype "passive"))
    )
    (net (code "107") (name "Net-(L28-K)") (class "Default")
      (node (ref "L28") (pin "2") (pinfunction "K_2") (pintype "passive"))
      (node (ref "U27") (pin "1") (pinfunction "A_1") (pintype "passive"))
    )
    (net (code "108") (name "Net-(L29-A)") (class "Default")
      (node (ref "L29") (pin "1") (pinfunction "A_1") (pintype "passive"))
      (node (ref "R77") (pin "1") (pinfunction "1_1") (pintype "passive"))
    )
    (net (code "109") (name "Net-(L30-A)") (class "Default")
      (node (ref "L30") (pin "1") (pinfunction "A_1") (pintype "passive"))
      (node (ref "R78") (pin "1") (pinfunction "1_1") (pintype "passive"))
    )
    (net (code "110") (name "Net-(Q1-B)") (class "Default")
      (node (ref "Q1") (pin "3") (pinfunction "B_3") (pintype "passive"))
      (node (ref "R10") (pin "1") (pinfunction "1_1") (pintype "passive"))
      (node (ref "R17") (pin "1") (pinfunction "1_1") (pintype "passive"))
    )
    (net (code "111") (name "Net-(Q2-B)") (class "Default")
      (node (ref "Q2") (pin "3") (pinfunction "B_3") (pintype "passive"))
      (node (ref "R18") (pin "1") (pinfunction "1_1") (pintype "passive"))
      (node (ref "R9") (pin "1") (pinfunction "1_1") (pintype "passive"))
    )
    (net (code "112") (name "Net-(Q3-B)") (class "Default")
      (node (ref "Q3") (pin "3") (pinfunction "B_3") (pintype "passive"))
      (node (ref "R13") (pin "1") (pinfunction "1_1") (pintype "passive"))
      (node (ref "R21") (pin "1") (pinfunction "1_1") (pintype "passive"))
    )
    (net (code "113") (name "Net-(Q4-B)") (class "Default")
      (node (ref "Q4") (pin "3") (pinfunction "B_3") (pintype "passive"))
      (node (ref "R25") (pin "1") (pinfunction "1_1") (pintype "passive"))
      (node (ref "R31") (pin "1") (pinfunction "1_1") (pintype "passive"))
    )
    (net (code "114") (name "Net-(Q5-B)") (class "Default")
      (node (ref "Q5") (pin "3") (pinfunction "B_3") (pintype "passive"))
      (node (ref "R26") (pin "1") (pinfunction "1_1") (pintype "passive"))
      (node (ref "R33") (pin "1") (pinfunction "1_1") (pintype "passive"))
    )
    (net (code "115") (name "Net-(Q6-B)") (class "Default")
      (node (ref "Q6") (pin "3") (pinfunction "B_3") (pintype "passive"))
      (node (ref "R27") (pin "1") (pinfunction "1_1") (pintype "passive"))
      (node (ref "R35") (pin "1") (pinfunction "1_1") (pintype "passive"))
    )
    (net (code "116") (name "Net-(Q7-B)") (class "Default")
      (node (ref "Q7") (pin "3") (pinfunction "B_3") (pintype "passive"))
      (node (ref "R39") (pin "1") (pinfunction "1_1") (pintype "passive"))
      (node (ref "R42") (pin "1") (pinfunction "1_1") (pintype "passive"))
    )
    (net (code "117") (name "Net-(Q8-B)") (class "Default")
      (node (ref "Q8") (pin "3") (pinfunction "B_3") (pintype "passive"))
      (node (ref "R40") (pin "1") (pinfunction "1_1") (pintype "passive"))
      (node (ref "R46") (pin "1") (pinfunction "1_1") (pintype "passive"))
    )
    (net (code "118") (name "Net-(Q9-B)") (class "Default")
      (node (ref "Q9") (pin "3") (pinfunction "B_3") (pintype "passive"))
      (node (ref "R49") (pin "1") (pinfunction "1_1") (pintype "passive"))
      (node (ref "R52") (pin "1") (pinfunction "1_1") (pintype "passive"))
    )
    (net (code "119") (name "Net-(Q10-B)") (class "Default")
      (node (ref "Q10") (pin "3") (pinfunction "B_3") (pintype "passive"))
      (node (ref "R50") (pin "1") (pinfunction "1_1") (pintype "passive"))
      (node (ref "R54") (pin "1") (pinfunction "1_1") (pintype "passive"))
    )
    (net (code "120") (name "Net-(Q11-B)") (class "Default")
      (node (ref "Q11") (pin "3") (pinfunction "B_3") (pintype "passive"))
      (node (ref "R59") (pin "1") (pinfunction "1_1") (pintype "passive"))
      (node (ref "R62") (pin "1") (pinfunction "1_1") (pintype "passive"))
    )
    (net (code "121") (name "Net-(Q12-B)") (class "Default")
      (node (ref "Q12") (pin "3") (pinfunction "B_3") (pintype "passive"))
      (node (ref "R60") (pin "1") (pinfunction "1_1") (pintype "passive"))
      (node (ref "R64") (pin "1") (pinfunction "1_1") (pintype "passive"))
    )
    (net (code "122") (name "Net-(Q13-B)") (class "Default")
      (node (ref "Q13") (pin "3") (pinfunction "B_3") (pintype "passive"))
      (node (ref "R69") (pin "1") (pinfunction "1_1") (pintype "passive"))
      (node (ref "R72") (pin "1") (pinfunction "1_1") (pintype "passive"))
    )
    (net (code "123") (name "Net-(Q14-B)") (class "Default")
      (node (ref "Q14") (pin "3") (pinfunction "B_3") (pintype "passive"))
      (node (ref "R70") (pin "1") (pinfunction "1_1") (pintype "passive"))
      (node (ref "R76") (pin "1") (pinfunction "1_1") (pintype "passive"))
    )
    (net (code "124") (name "Net-(U1-BOOT0)") (class "Default")
      (node (ref "R3") (pin "1") (pinfunction "1_1") (pintype "passive"))
      (node (ref "U1") (pin "44") (pinfunction "BOOT0_44") (pintype "passive"))
    )
    (net (code "125") (name "Net-(U1-NRST)") (class "Default")
      (node (ref "BT1") (pin "2") (pinfunction "2_2") (pintype "passive"))
      (node (ref "C12") (pin "1") (pinfunction "1_1") (pintype "passive"))
      (node (ref "R8") (pin "1") (pinfunction "1_1") (pintype "passive"))
      (node (ref "U1") (pin "7") (pinfunction "NRST_7") (pintype "passive"))
    )
    (net (code "126") (name "Net-(U1-PD0-OSC_IN)") (class "Default")
      (node (ref "C8") (pin "1") (pinfunction "1_1") (pintype "passive"))
      (node (ref "U1") (pin "5") (pinfunction "PD0-OSC_IN_5") (pintype "passive"))
      (node (ref "Y1") (pin "1") (pinfunction "1_1") (pintype "passive"))
    )
    (net (code "127") (name "Net-(U1-PD1-OSC_OUT)") (class "Default")
      (node (ref "C9") (pin "1") (pinfunction "1_1") (pintype "passive"))
      (node (ref "U1") (pin "6") (pinfunction "PD1-OSC_OUT_6") (pintype "passive"))
      (node (ref "Y1") (pin "2") (pinfunction "2_2") (pintype "passive"))
    )
    (net (code "128") (name "Net-(U4-A)") (class "Default")
      (node (ref "R19") (pin "2") (pinfunction "2_2") (pintype "passive"))
      (node (ref "U4") (pin "1") (pinfunction "A_1") (pintype "passive"))
    )
    (net (code "129") (name "Net-(U4-C)") (class "Default")
      (node (ref "R17") (pin "2") (pinfunction "2_2") (pintype "passive"))
      (node (ref "U4") (pin "4") (pinfunction "C_4") (pintype "passive"))
    )
    (net (code "130") (name "Net-(U5-A)") (class "Default")
      (node (ref "R16") (pin "2") (pinfunction "2_2") (pintype "passive"))
      (node (ref "U5") (pin "1") (pinfunction "A_1") (pintype "passive"))
    )
    (net (code "131") (name "Net-(U5-C)") (class "Default")
      (node (ref "R18") (pin "2") (pinfunction "2_2") (pintype "passive"))
      (node (ref "U5") (pin "4") (pinfunction "C_4") (pintype "passive"))
    )
    (net (code "132") (name "Net-(U6-A)") (class "Default")
      (node (ref "R20") (pin "2") (pinfunction "2_2") (pintype "passive"))
      (node (ref "U6") (pin "1") (pinfunction "A_1") (pintype "passive"))
    )
    (net (code "133") (name "Net-(U6-C)") (class "Default")
      (node (ref "R21") (pin "2") (pinfunction "2_2") (pintype "passive"))
      (node (ref "U6") (pin "4") (pinfunction "C_4") (pintype "passive"))
    )
    (net (code "134") (name "Net-(U9-A)") (class "Default")
      (node (ref "R28") (pin "2") (pinfunction "2_2") (pintype "passive"))
      (node (ref "U9") (pin "1") (pinfunction "A_1") (pintype "passive"))
    )
    (net (code "135") (name "Net-(U9-C)") (class "Default")
      (node (ref "R31") (pin "2") (pinfunction "2_2") (pintype "passive"))
      (node (ref "U9") (pin "4") (pinfunction "C_4") (pintype "passive"))
    )
    (net (code "136") (name "Net-(U10-A)") (class "Default")
      (node (ref "R32") (pin "2") (pinfunction "2_2") (pintype "passive"))
      (node (ref "U10") (pin "1") (pinfunction "A_1") (pintype "passive"))
    )
    (net (code "137") (name "Net-(U10-C)") (class "Default")
      (node (ref "R33") (pin "2") (pinfunction "2_2") (pintype "passive"))
      (node (ref "U10") (pin "4") (pinfunction "C_4") (pintype "passive"))
    )
    (net (code "138") (name "Net-(U11-A)") (class "Default")
      (node (ref "R34") (pin "2") (pinfunction "2_2") (pintype "passive"))
      (node (ref "U11") (pin "1") (pinfunction "A_1") (pintype "passive"))
    )
    (net (code "139") (name "Net-(U11-C)") (class "Default")
      (node (ref "R35") (pin "2") (pinfunction "2_2") (pintype "passive"))
      (node (ref "U11") (pin "4") (pinfunction "C_4") (pintype "passive"))
    )
    (net (code "140") (name "Net-(U14-A)") (class "Default")
      (node (ref "R41") (pin "2") (pinfunction "2_2") (pintype "passive"))
      (node (ref "U14") (pin "1") (pinfunction "A_1") (pintype "passive"))
    )
    (net (code "141") (name "Net-(U14-C)") (class "Default")
      (node (ref "R42") (pin "2") (pinfunction "2_2") (pintype "passive"))
      (node (ref "U14") (pin "4") (pinfunction "C_4") (pintype "passive"))
    )
    (net (code "142") (name "Net-(U15-A)") (class "Default")
      (node (ref "R45") (pin "2") (pinfunction "2_2") (pintype "passive"))
      (node (ref "U15") (pin "1") (pinfunction "A_1") (pintype "passive"))
    )
    (net (code "143") (name "Net-(U15-C)") (class "Default")
      (node (ref "R46") (pin "2") (pinfunction "2_2") (pintype "passive"))
      (node (ref "U15") (pin "4") (pinfunction "C_4") (pintype "passive"))
    )
    (net (code "144") (name "Net-(U18-A)") (class "Default")
      (node (ref "R51") (pin "2") (pinfunction "2_2") (pintype "passive"))
      (node (ref "U18") (pin "1") (pinfunction "A_1") (pintype "passive"))
    )
    (net (code "145") (name "Net-(U18-C)") (class "Default")
      (node (ref "R52") (pin "2") (pinfunction "2_2") (pintype "passive"))
      (node (ref "U18") (pin "4") (pinfunction "C_4") (pintype "passive"))
    )
    (net (code "146") (name "Net-(U19-A)") (class "Default")
      (node (ref "R53") (pin "2") (pinfunction "2_2") (pintype "passive"))
      (node (ref "U19") (pin "1") (pinfunction "A_1") (pintype "passive"))
    )
    (net (code "147") (name "Net-(U19-C)") (class "Default")
      (node (ref "R54") (pin "2") (pinfunction "2_2") (pintype "passive"))
      (node (ref "U19") (pin "4") (pinfunction "C_4") (pintype "passive"))
    )
    (net (code "148") (name "Net-(U24-A)") (class "Default")
      (node (ref "R61") (pin "2") (pinfunction "2_2") (pintype "passive"))
      (node (ref "U24") (pin "1") (pinfunction "A_1") (pintype "passive"))
    )
    (net (code "149") (name "Net-(U24-C)") (class "Default")
      (node (ref "R62") (pin "2") (pinfunction "2_2") (pintype "passive"))
      (node (ref "U24") (pin "4") (pinfunction "C_4") (pintype "passive"))
    )
    (net (code "150") (name "Net-(U25-A)") (class "Default")
      (node (ref "R63") (pin "2") (pinfunction "2_2") (pintype "passive"))
      (node (ref "U25") (pin "1") (pinfunction "A_1") (pintype "passive"))
    )
    (net (code "151") (name "Net-(U25-C)") (class "Default")
      (node (ref "R64") (pin "2") (pinfunction "2_2") (pintype "passive"))
      (node (ref "U25") (pin "4") (pinfunction "C_4") (pintype "passive"))
    )
    (net (code "152") (name "Net-(U28-A)") (class "Default")
      (node (ref "R71") (pin "2") (pinfunction "2_2") (pintype "passive"))
      (node (ref "U28") (pin "1") (pinfunction "A_1") (pintype "passive"))
    )
    (net (code "153") (name "Net-(U28-C)") (class "Default")
      (node (ref "R72") (pin "2") (pinfunction "2_2") (pintype "passive"))
      (node (ref "U28") (pin "4") (pinfunction "C_4") (pintype "passive"))
    )
    (net (code "154") (name "Net-(U29-A)") (class "Default")
      (node (ref "R75") (pin "2") (pinfunction "2_2") (pintype "passive"))
      (node (ref "U29") (pin "1") (pinfunction "A_1") (pintype "passive"))
    )
    (net (code "155") (name "Net-(U29-C)") (class "Default")
      (node (ref "R76") (pin "2") (pinfunction "2_2") (pintype "passive"))
      (node (ref "U29") (pin "4") (pinfunction "C_4") (pintype "passive"))
    )
    (net (code "156") (name "unconnected-(L10-A-Pad1)") (class "Default")
      (node (ref "L10") (pin "1") (pinfunction "A_1") (pintype "passive"))
    )
    (net (code "157") (name "unconnected-(L11-A-Pad1)") (class "Default")
      (node (ref "L11") (pin "1") (pinfunction "A_1") (pintype "passive"))
    )
    (net (code "158") (name "unconnected-(L12-A-Pad1)") (class "Default")
      (node (ref "L12") (pin "1") (pinfunction "A_1") (pintype "passive"))
    )
    (net (code "159") (name "unconnected-(R36-Pad1)") (class "Default")
      (node (ref "R36") (pin "1") (pinfunction "1_1") (pintype "passive"))
    )
    (net (code "160") (name "unconnected-(R37-Pad1)") (class "Default")
      (node (ref "R37") (pin "1") (pinfunction "1_1") (pintype "passive"))
    )
    (net (code "161") (name "unconnected-(R38-Pad1)") (class "Default")
      (node (ref "R38") (pin "1") (pinfunction "1_1") (pintype "passive"))
    )
    (net (code "162") (name "unconnected-(R53-Pad1)") (class "Default")
      (node (ref "R53") (pin "1") (pinfunction "1_1") (pintype "passive"))
    )
    (net (code "163") (name "unconnected-(R63-Pad1)") (class "Default")
      (node (ref "R63") (pin "1") (pinfunction "1_1") (pintype "passive"))
    )
    (net (code "164") (name "unconnected-(U1-PA0-WKUP-Pad10)") (class "Default")
      (node (ref "U1") (pin "10") (pinfunction "PA0-WKUP_10") (pintype "passive+no_connect"))
    )
    (net (code "165") (name "unconnected-(U1-PA8-Pad29)") (class "Default")
      (node (ref "U1") (pin "29") (pinfunction "PA8_29") (pintype "passive+no_connect"))
    )
    (net (code "166") (name "unconnected-(U1-PA9-Pad30)") (class "Default")
      (node (ref "U1") (pin "30") (pinfunction "PA9_30") (pintype "passive+no_connect"))
    )
  )
)
